# FPGA.net
KiCad netlist of a schematic drawn in Altium Designer
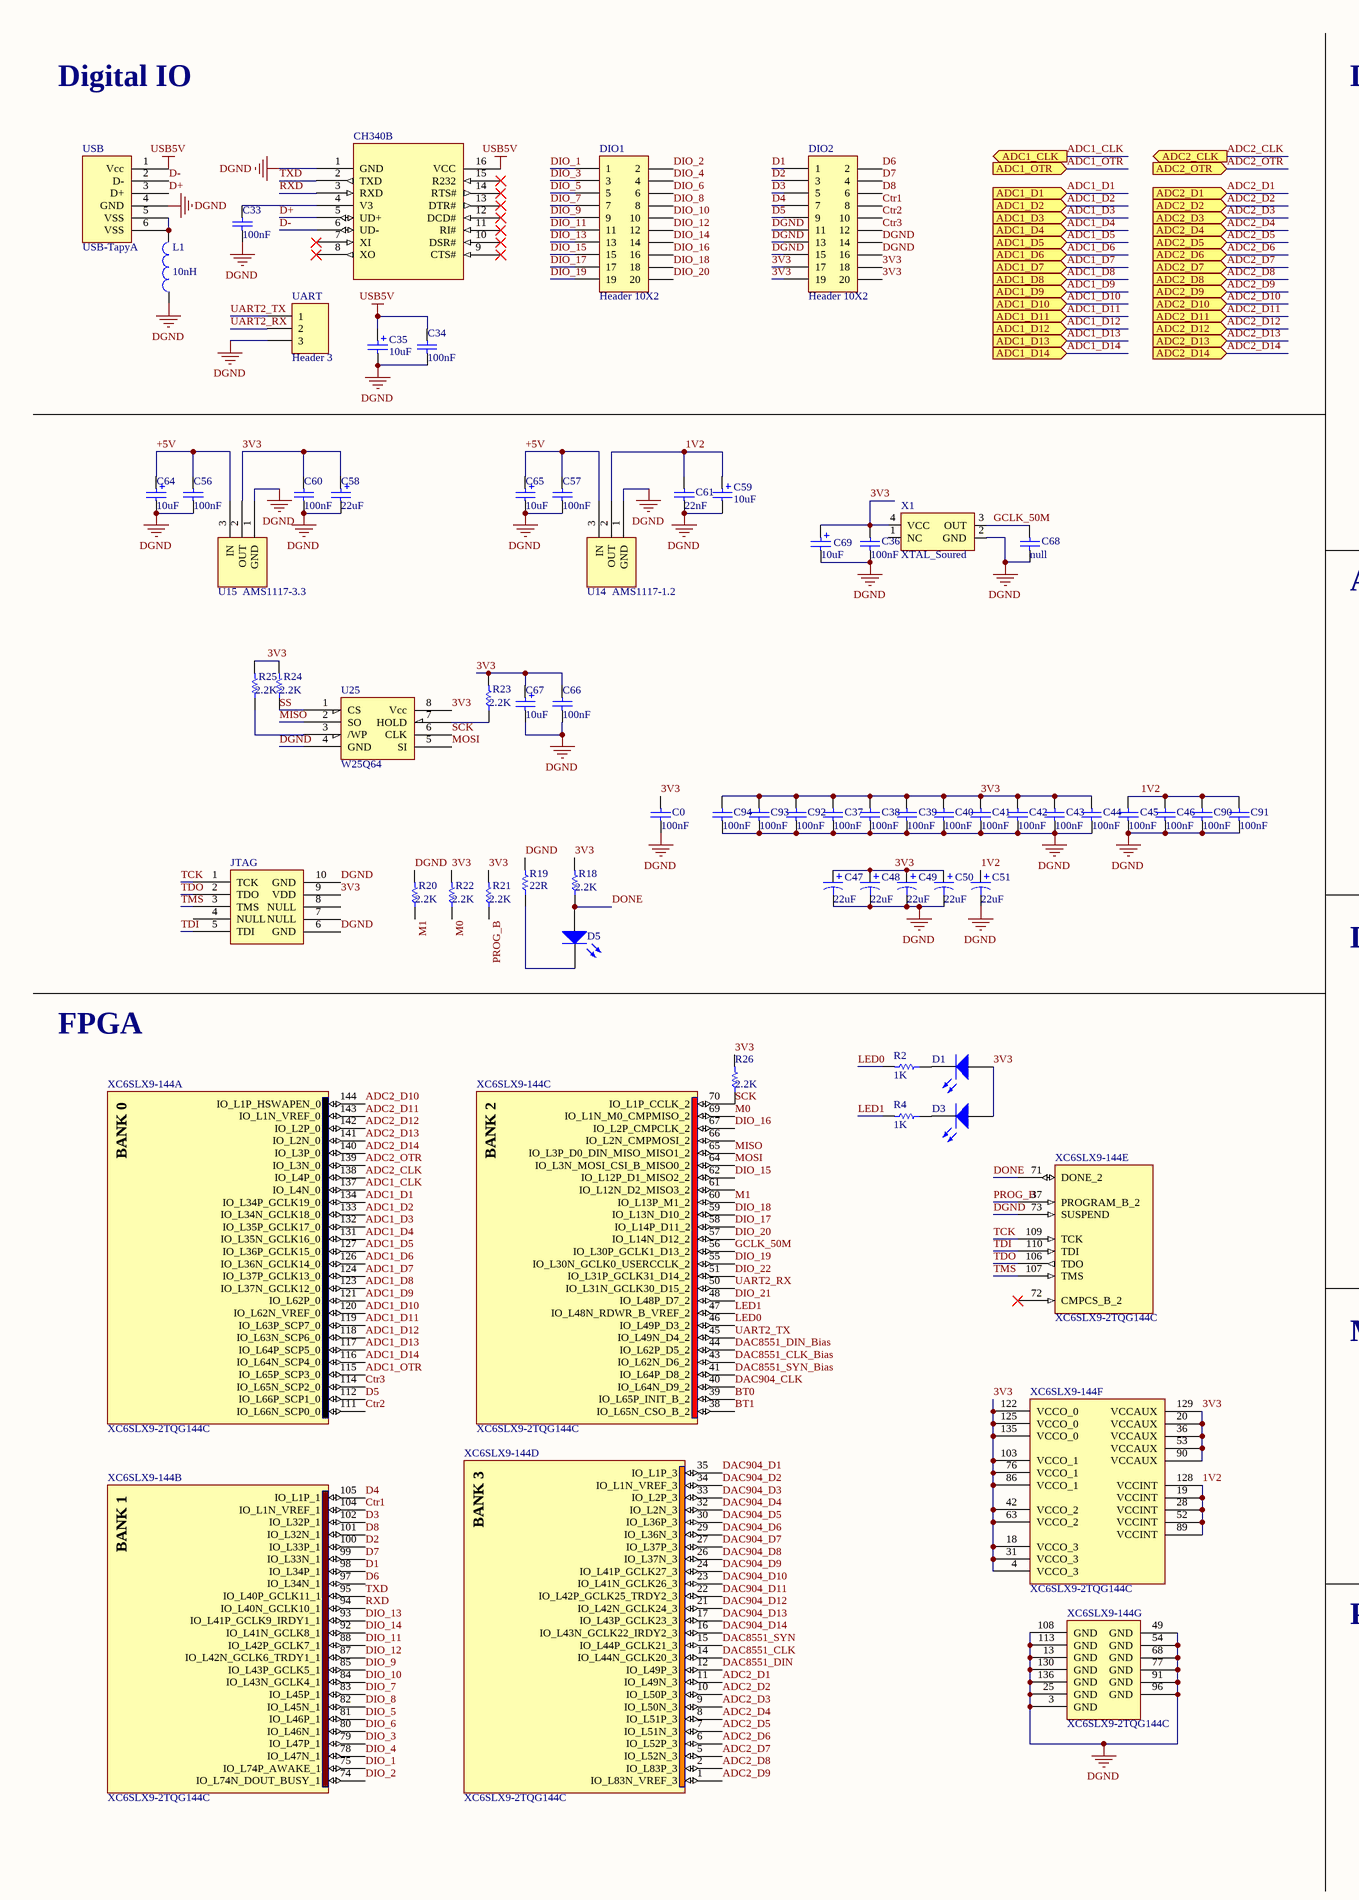
[diagram p0: FPGA.SchDoc, left]
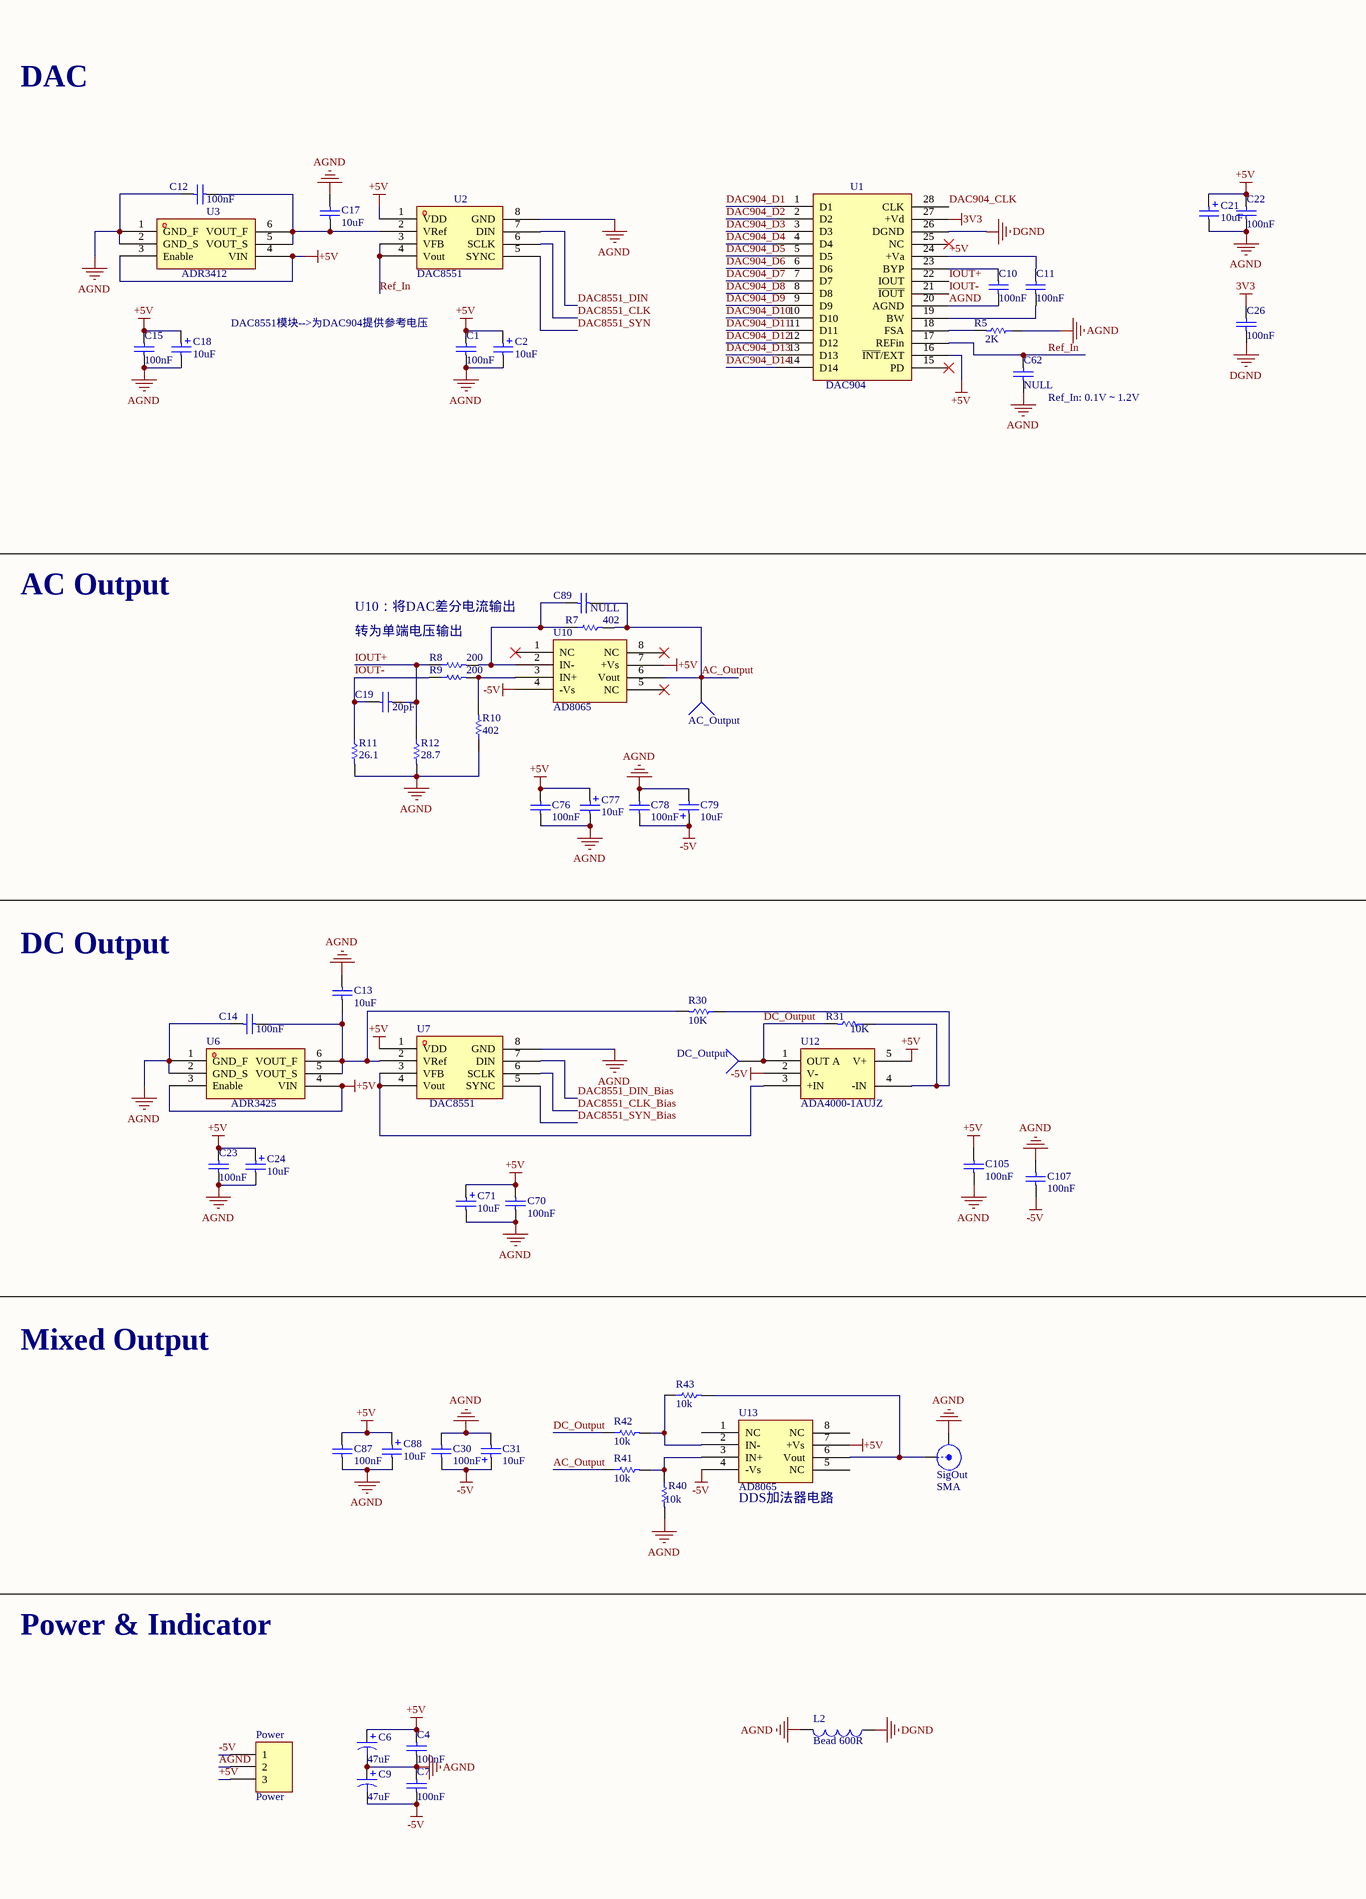
[diagram p1: FPGA.SchDoc, right]

(export (version "E")
  (design (tool "Eeschema 10.0.6"))
  (components
    (comp (ref "AC_Output")
      (value "OutDir")
      (footprint "PIN1")
      (description "Socket")
      (fields (field (name "PUBLISHER") "Altium Limited"))
      (libsource (lib "Miscellaneous Connectors") (part "Socket"))
    )
    (comp (ref "C0")
      (value "100nF")
      (footprint "BinFeng:0603")
      (description "Capacitor")
      (fields (field (name "PUBLISHER") "Altium Limited"))
      (libsource (lib "Miscellaneous Devices") (part "Cap"))
    )
    (comp (ref "C1")
      (value "100nF")
      (footprint "BinFeng:0603")
      (description "Capacitor (Semiconductor SIM Model)")
      (fields (field (name "PUBLISHER") "Altium Limited"))
      (libsource (lib "Miscellaneous Devices") (part "Cap Semi"))
    )
    (comp (ref "C2")
      (value "10uF")
      (footprint "3216")
      (description "Polarized Capacitor (Axial)")
      (fields (field (name "PUBLISHER") "Altium Limited"))
      (libsource (lib "Miscellaneous Devices") (part "Cap Pol2"))
    )
    (comp (ref "C4")
      (value "100nF")
      (footprint "SEEDER:0603")
      (description "Capacitor (Semiconductor SIM Model)")
      (fields (field (name "PUBLISHER") "Altium Limited"))
      (libsource (lib "Miscellaneous Devices") (part "Cap Semi"))
    )
    (comp (ref "C6")
      (value "47uF")
      (footprint "cap_pol_8*10.2")
      (description "Polarized Capacitor (Surface Mount)")
      (fields (field (name "PUBLISHER") "Altium Limited"))
      (libsource (lib "Miscellaneous Devices") (part "Cap Pol3"))
    )
    (comp (ref "C7")
      (value "100nF")
      (footprint "SEEDER:0603")
      (description "Capacitor (Semiconductor SIM Model)")
      (fields (field (name "PUBLISHER") "Altium Limited"))
      (libsource (lib "Miscellaneous Devices") (part "Cap Semi"))
    )
    (comp (ref "C9")
      (value "47uF")
      (footprint "cap_pol_8*10.2")
      (description "Polarized Capacitor (Surface Mount)")
      (fields (field (name "PUBLISHER") "Altium Limited"))
      (libsource (lib "Miscellaneous Devices") (part "Cap Pol3"))
    )
    (comp (ref "C10")
      (value "100nF")
      (footprint "BinFeng:0603")
      (description "Capacitor (Semiconductor SIM Model)")
      (fields (field (name "PUBLISHER") "Altium Limited"))
      (libsource (lib "Miscellaneous Devices") (part "Cap Semi"))
    )
    (comp (ref "C11")
      (value "100nF")
      (footprint "BinFeng:0603")
      (description "Capacitor (Semiconductor SIM Model)")
      (fields (field (name "PUBLISHER") "Altium Limited"))
      (libsource (lib "Miscellaneous Devices") (part "Cap Semi"))
    )
    (comp (ref "C12")
      (value "100nF")
      (footprint "BinFeng:0603")
      (description "Capacitor (Semiconductor SIM Model)")
      (fields (field (name "PUBLISHER") "Altium Limited"))
      (libsource (lib "Miscellaneous Devices") (part "Cap Semi"))
    )
    (comp (ref "C13")
      (value "10uF")
      (footprint "0805")
      (description "Capacitor (Semiconductor SIM Model)")
      (fields (field (name "PUBLISHER") "Altium Limited"))
      (libsource (lib "Miscellaneous Devices") (part "Cap Semi"))
    )
    (comp (ref "C14")
      (value "100nF")
      (footprint "BinFeng:0603")
      (description "Capacitor (Semiconductor SIM Model)")
      (fields (field (name "PUBLISHER") "Altium Limited"))
      (libsource (lib "Miscellaneous Devices") (part "Cap Semi"))
    )
    (comp (ref "C15")
      (value "100nF")
      (footprint "BinFeng:0603")
      (description "Capacitor (Semiconductor SIM Model)")
      (fields (field (name "PUBLISHER") "Altium Limited"))
      (libsource (lib "Miscellaneous Devices") (part "Cap Semi"))
    )
    (comp (ref "C17")
      (value "10uF")
      (footprint "0805")
      (description "Capacitor (Semiconductor SIM Model)")
      (fields (field (name "Comment") "100nF") (field (name "PUBLISHER") "Altium Limited"))
      (libsource (lib "Miscellaneous Devices") (part "Cap Semi"))
    )
    (comp (ref "C18")
      (value "10uF")
      (footprint "3216")
      (description "Polarized Capacitor (Axial)")
      (fields (field (name "PUBLISHER") "Altium Limited"))
      (libsource (lib "Miscellaneous Devices") (part "Cap Pol2"))
    )
    (comp (ref "C19")
      (value "20pF")
      (footprint "BinFeng:0603")
      (description "Capacitor (Semiconductor SIM Model)")
      (fields (field (name "PUBLISHER") "Altium Limited"))
      (libsource (lib "Miscellaneous Devices") (part "Cap Semi"))
    )
    (comp (ref "C21")
      (value "10uF")
      (footprint "3216")
      (description "Polarized Capacitor (Axial)")
      (fields (field (name "PUBLISHER") "Altium Limited"))
      (libsource (lib "Miscellaneous Devices") (part "Cap Pol2"))
    )
    (comp (ref "C22")
      (value "100nF")
      (footprint "BinFeng:0603")
      (description "Capacitor (Semiconductor SIM Model)")
      (fields (field (name "PUBLISHER") "Altium Limited"))
      (libsource (lib "Miscellaneous Devices") (part "Cap Semi"))
    )
    (comp (ref "C23")
      (value "100nF")
      (footprint "BinFeng:0603")
      (description "Capacitor (Semiconductor SIM Model)")
      (fields (field (name "PUBLISHER") "Altium Limited"))
      (libsource (lib "Miscellaneous Devices") (part "Cap Semi"))
    )
    (comp (ref "C24")
      (value "10uF")
      (footprint "3216")
      (description "Polarized Capacitor (Axial)")
      (fields (field (name "PUBLISHER") "Altium Limited"))
      (libsource (lib "Miscellaneous Devices") (part "Cap Pol2"))
    )
    (comp (ref "C26")
      (value "100nF")
      (footprint "BinFeng:0603")
      (description "Capacitor (Semiconductor SIM Model)")
      (fields (field (name "PUBLISHER") "Altium Limited"))
      (libsource (lib "Miscellaneous Devices") (part "Cap Semi"))
    )
    (comp (ref "C30")
      (value "100nF")
      (footprint "BinFeng:0603")
      (description "Capacitor (Semiconductor SIM Model)")
      (fields (field (name "PUBLISHER") "Altium Limited"))
      (libsource (lib "Miscellaneous Devices") (part "Cap Semi"))
    )
    (comp (ref "C31")
      (value "10uF")
      (footprint "3216")
      (description "Polarized Capacitor (Axial)")
      (fields (field (name "PUBLISHER") "Altium Limited"))
      (libsource (lib "Miscellaneous Devices") (part "Cap Pol2"))
    )
    (comp (ref "C33")
      (value "100nF")
      (footprint "SEEDER:0603")
      (description "Capacitor (Semiconductor SIM Model)")
      (fields (field (name "PUBLISHER") "Altium Limited"))
      (libsource (lib "Miscellaneous Devices") (part "Cap Semi"))
    )
    (comp (ref "C34")
      (value "100nF")
      (footprint "SEEDER:0603")
      (description "Capacitor (Semiconductor SIM Model)")
      (fields (field (name "PUBLISHER") "Altium Limited"))
      (libsource (lib "Miscellaneous Devices") (part "Cap Semi"))
    )
    (comp (ref "C35")
      (value "10uF")
      (footprint "3216")
      (description "Polarized Capacitor (Axial)")
      (fields (field (name "PUBLISHER") "Altium Limited"))
      (libsource (lib "Miscellaneous Devices") (part "Cap Pol2"))
    )
    (comp (ref "C36")
      (value "100nF")
      (footprint "BinFeng:0603")
      (description "Capacitor")
      (fields (field (name "PUBLISHER") "Altium Limited"))
      (libsource (lib "Miscellaneous Devices") (part "Cap"))
    )
    (comp (ref "C37")
      (value "100nF")
      (footprint "BinFeng:0603")
      (description "Capacitor")
      (fields (field (name "PUBLISHER") "Altium Limited"))
      (libsource (lib "Miscellaneous Devices") (part "Cap"))
    )
    (comp (ref "C38")
      (value "100nF")
      (footprint "BinFeng:0603")
      (description "Capacitor")
      (fields (field (name "PUBLISHER") "Altium Limited"))
      (libsource (lib "Miscellaneous Devices") (part "Cap"))
    )
    (comp (ref "C39")
      (value "100nF")
      (footprint "BinFeng:0603")
      (description "Capacitor")
      (fields (field (name "PUBLISHER") "Altium Limited"))
      (libsource (lib "Miscellaneous Devices") (part "Cap"))
    )
    (comp (ref "C40")
      (value "100nF")
      (footprint "BinFeng:0603")
      (description "Capacitor")
      (fields (field (name "PUBLISHER") "Altium Limited"))
      (libsource (lib "Miscellaneous Devices") (part "Cap"))
    )
    (comp (ref "C41")
      (value "100nF")
      (footprint "BinFeng:0603")
      (description "Capacitor")
      (fields (field (name "PUBLISHER") "Altium Limited"))
      (libsource (lib "Miscellaneous Devices") (part "Cap"))
    )
    (comp (ref "C42")
      (value "100nF")
      (footprint "BinFeng:0603")
      (description "Capacitor")
      (fields (field (name "PUBLISHER") "Altium Limited"))
      (libsource (lib "Miscellaneous Devices") (part "Cap"))
    )
    (comp (ref "C43")
      (value "100nF")
      (footprint "BinFeng:0603")
      (description "Capacitor")
      (fields (field (name "PUBLISHER") "Altium Limited"))
      (libsource (lib "Miscellaneous Devices") (part "Cap"))
    )
    (comp (ref "C44")
      (value "100nF")
      (footprint "BinFeng:0603")
      (description "Capacitor")
      (fields (field (name "PUBLISHER") "Altium Limited"))
      (libsource (lib "Miscellaneous Devices") (part "Cap"))
    )
    (comp (ref "C45")
      (value "100nF")
      (footprint "BinFeng:0603")
      (description "Capacitor")
      (fields (field (name "PUBLISHER") "Altium Limited"))
      (libsource (lib "Miscellaneous Devices") (part "Cap"))
    )
    (comp (ref "C46")
      (value "100nF")
      (footprint "BinFeng:0603")
      (description "Capacitor")
      (fields (field (name "PUBLISHER") "Altium Limited"))
      (libsource (lib "Miscellaneous Devices") (part "Cap"))
    )
    (comp (ref "C47")
      (value "22uF")
      (footprint "3216")
      (description "Polarized Capacitor (Surface Mount)")
      (fields (field (name "PUBLISHER") "Altium Limited"))
      (libsource (lib "Miscellaneous Devices") (part "Cap Pol3"))
    )
    (comp (ref "C48")
      (value "22uF")
      (footprint "3216")
      (description "Polarized Capacitor (Surface Mount)")
      (fields (field (name "PUBLISHER") "Altium Limited"))
      (libsource (lib "Miscellaneous Devices") (part "Cap Pol3"))
    )
    (comp (ref "C49")
      (value "22uF")
      (footprint "3216")
      (description "Polarized Capacitor (Surface Mount)")
      (fields (field (name "PUBLISHER") "Altium Limited"))
      (libsource (lib "Miscellaneous Devices") (part "Cap Pol3"))
    )
    (comp (ref "C50")
      (value "22uF")
      (footprint "3216")
      (description "Polarized Capacitor (Surface Mount)")
      (fields (field (name "PUBLISHER") "Altium Limited"))
      (libsource (lib "Miscellaneous Devices") (part "Cap Pol3"))
    )
    (comp (ref "C51")
      (value "22uF")
      (footprint "3216")
      (description "Polarized Capacitor (Surface Mount)")
      (fields (field (name "PUBLISHER") "Altium Limited"))
      (libsource (lib "Miscellaneous Devices") (part "Cap Pol3"))
    )
    (comp (ref "C56")
      (value "100nF")
      (footprint "BinFeng:0603")
      (description "Capacitor")
      (fields (field (name "PUBLISHER") "Altium Limited"))
      (libsource (lib "Miscellaneous Devices") (part "Cap"))
    )
    (comp (ref "C57")
      (value "100nF")
      (footprint "BinFeng:0603")
      (description "Capacitor")
      (fields (field (name "PUBLISHER") "Altium Limited"))
      (libsource (lib "Miscellaneous Devices") (part "Cap"))
    )
    (comp (ref "C58")
      (value "22uF")
      (footprint "3216")
      (description "Polarized Capacitor (Axial)")
      (fields (field (name "Comment") "10uF") (field (name "PUBLISHER") "Altium Limited"))
      (libsource (lib "Miscellaneous Devices") (part "Cap Pol2"))
    )
    (comp (ref "C59")
      (value "10uF")
      (footprint "3216")
      (description "Polarized Capacitor (Axial)")
      (fields (field (name "PUBLISHER") "Altium Limited"))
      (libsource (lib "Miscellaneous Devices") (part "Cap Pol2"))
    )
    (comp (ref "C60")
      (value "100nF")
      (footprint "BinFeng:0603")
      (description "Capacitor")
      (fields (field (name "PUBLISHER") "Altium Limited"))
      (libsource (lib "Miscellaneous Devices") (part "Cap"))
    )
    (comp (ref "C61")
      (value "22nF")
      (footprint "BinFeng:0603")
      (description "Capacitor")
      (fields (field (name "PUBLISHER") "Altium Limited"))
      (libsource (lib "Miscellaneous Devices") (part "Cap"))
    )
    (comp (ref "C62")
      (value "NULL")
      (footprint "BinFeng:0603")
      (description "Capacitor (Semiconductor SIM Model)")
      (fields (field (name "Comment") "100nF") (field (name "PUBLISHER") "Altium Limited"))
      (libsource (lib "Miscellaneous Devices") (part "Cap Semi"))
    )
    (comp (ref "C64")
      (value "10uF")
      (footprint "3216")
      (description "Polarized Capacitor (Axial)")
      (fields (field (name "PUBLISHER") "Altium Limited"))
      (libsource (lib "Miscellaneous Devices") (part "Cap Pol2"))
    )
    (comp (ref "C65")
      (value "10uF")
      (footprint "3216")
      (description "Polarized Capacitor (Axial)")
      (fields (field (name "PUBLISHER") "Altium Limited"))
      (libsource (lib "Miscellaneous Devices") (part "Cap Pol2"))
    )
    (comp (ref "C66")
      (value "100nF")
      (footprint "BinFeng:0603")
      (description "Capacitor")
      (fields (field (name "PUBLISHER") "Altium Limited"))
      (libsource (lib "Miscellaneous Devices") (part "Cap"))
    )
    (comp (ref "C67")
      (value "10uF")
      (footprint "3216")
      (description "Polarized Capacitor (Axial)")
      (fields (field (name "PUBLISHER") "Altium Limited"))
      (libsource (lib "Miscellaneous Devices") (part "Cap Pol2"))
    )
    (comp (ref "C68")
      (value "null")
      (footprint "BinFeng:0603")
      (description "Capacitor")
      (fields (field (name "Comment") "100nF") (field (name "PUBLISHER") "Altium Limited"))
      (libsource (lib "Miscellaneous Devices") (part "Cap"))
    )
    (comp (ref "C69")
      (value "10uF")
      (footprint "3216")
      (description "Polarized Capacitor (Axial)")
      (fields (field (name "PUBLISHER") "Altium Limited"))
      (libsource (lib "Miscellaneous Devices") (part "Cap Pol2"))
    )
    (comp (ref "C70")
      (value "100nF")
      (footprint "BinFeng:0603")
      (description "Capacitor (Semiconductor SIM Model)")
      (fields (field (name "PUBLISHER") "Altium Limited"))
      (libsource (lib "Miscellaneous Devices") (part "Cap Semi"))
    )
    (comp (ref "C71")
      (value "10uF")
      (footprint "3216")
      (description "Polarized Capacitor (Axial)")
      (fields (field (name "PUBLISHER") "Altium Limited"))
      (libsource (lib "Miscellaneous Devices") (part "Cap Pol2"))
    )
    (comp (ref "C76")
      (value "100nF")
      (footprint "BinFeng:0603")
      (description "Capacitor (Semiconductor SIM Model)")
      (fields (field (name "PUBLISHER") "Altium Limited"))
      (libsource (lib "Miscellaneous Devices") (part "Cap Semi"))
    )
    (comp (ref "C77")
      (value "10uF")
      (footprint "3216")
      (description "Polarized Capacitor (Axial)")
      (fields (field (name "PUBLISHER") "Altium Limited"))
      (libsource (lib "Miscellaneous Devices") (part "Cap Pol2"))
    )
    (comp (ref "C78")
      (value "100nF")
      (footprint "BinFeng:0603")
      (description "Capacitor (Semiconductor SIM Model)")
      (fields (field (name "PUBLISHER") "Altium Limited"))
      (libsource (lib "Miscellaneous Devices") (part "Cap Semi"))
    )
    (comp (ref "C79")
      (value "10uF")
      (footprint "3216")
      (description "Polarized Capacitor (Axial)")
      (fields (field (name "PUBLISHER") "Altium Limited"))
      (libsource (lib "Miscellaneous Devices") (part "Cap Pol2"))
    )
    (comp (ref "C87")
      (value "100nF")
      (footprint "BinFeng:0603")
      (description "Capacitor (Semiconductor SIM Model)")
      (fields (field (name "PUBLISHER") "Altium Limited"))
      (libsource (lib "Miscellaneous Devices") (part "Cap Semi"))
    )
    (comp (ref "C88")
      (value "10uF")
      (footprint "3216")
      (description "Polarized Capacitor (Axial)")
      (fields (field (name "PUBLISHER") "Altium Limited"))
      (libsource (lib "Miscellaneous Devices") (part "Cap Pol2"))
    )
    (comp (ref "C89")
      (value "NULL")
      (footprint "BinFeng:0603")
      (description "Capacitor (Semiconductor SIM Model)")
      (fields (field (name "PUBLISHER") "Altium Limited"))
      (libsource (lib "Miscellaneous Devices") (part "Cap Semi"))
    )
    (comp (ref "C90")
      (value "100nF")
      (footprint "BinFeng:0603")
      (description "Capacitor")
      (fields (field (name "PUBLISHER") "Altium Limited"))
      (libsource (lib "Miscellaneous Devices") (part "Cap"))
    )
    (comp (ref "C91")
      (value "100nF")
      (footprint "BinFeng:0603")
      (description "Capacitor")
      (fields (field (name "PUBLISHER") "Altium Limited"))
      (libsource (lib "Miscellaneous Devices") (part "Cap"))
    )
    (comp (ref "C92")
      (value "100nF")
      (footprint "BinFeng:0603")
      (description "Capacitor")
      (fields (field (name "PUBLISHER") "Altium Limited"))
      (libsource (lib "Miscellaneous Devices") (part "Cap"))
    )
    (comp (ref "C93")
      (value "100nF")
      (footprint "BinFeng:0603")
      (description "Capacitor")
      (fields (field (name "PUBLISHER") "Altium Limited"))
      (libsource (lib "Miscellaneous Devices") (part "Cap"))
    )
    (comp (ref "C94")
      (value "100nF")
      (footprint "BinFeng:0603")
      (description "Capacitor")
      (fields (field (name "PUBLISHER") "Altium Limited"))
      (libsource (lib "Miscellaneous Devices") (part "Cap"))
    )
    (comp (ref "C105")
      (value "100nF")
      (footprint "BinFeng:0603")
      (description "Capacitor (Semiconductor SIM Model)")
      (fields (field (name "PUBLISHER") "Altium Limited"))
      (libsource (lib "Miscellaneous Devices") (part "Cap Semi"))
    )
    (comp (ref "C107")
      (value "100nF")
      (footprint "BinFeng:0603")
      (description "Capacitor (Semiconductor SIM Model)")
      (fields (field (name "PUBLISHER") "Altium Limited"))
      (libsource (lib "Miscellaneous Devices") (part "Cap Semi"))
    )
    (comp (ref "CH340B")
      (value "Comment")
      (footprint "PCBComponent_1")
      (description "USB to TTL Serial / UART")
      (libsource (lib "*") (part "CH340G"))
    )
    (comp (ref "D1")
      (value "LED3")
      (footprint "1206_LED")
      (description "Typical BLUE SiC LED")
      (fields (field (name "PUBLISHER") "Altium Limited"))
      (libsource (lib "Miscellaneous Devices") (part "LED3"))
    )
    (comp (ref "D3")
      (value "LED3")
      (footprint "1206_LED")
      (description "Typical BLUE SiC LED")
      (fields (field (name "PUBLISHER") "Altium Limited"))
      (libsource (lib "Miscellaneous Devices") (part "LED3"))
    )
    (comp (ref "D5")
      (value "LED3")
      (footprint "0805_pol1")
      (description "Typical BLUE SiC LED")
      (fields (field (name "PUBLISHER") "Altium Limited"))
      (libsource (lib "Miscellaneous Devices") (part "LED3"))
    )
    (comp (ref "DC_Output")
      (value "OutDir")
      (footprint "PIN1")
      (description "Socket")
      (fields (field (name "PUBLISHER") "Altium Limited"))
      (libsource (lib "Miscellaneous Connectors") (part "Socket"))
    )
    (comp (ref "DIO1")
      (value "Header 10X2")
      (footprint "HDR2X10")
      (description "Header, 10-Pin, Dual row")
      (fields (field (name "PUBLISHER") "Altium Limited"))
      (libsource (lib "Miscellaneous Connectors") (part "Header 10X2"))
    )
    (comp (ref "DIO2")
      (value "Header 10X2")
      (footprint "HDR2X10")
      (description "Header, 10-Pin, Dual row")
      (fields (field (name "PUBLISHER") "Altium Limited"))
      (libsource (lib "Miscellaneous Connectors") (part "Header 10X2"))
    )
    (comp (ref "JTAG")
      (value "JTAG 2*5p 2.00mm 180 degree")
      (footprint "JTAG_2.54_2x5")
      (libsource (lib "BinFeng_IC") (part "FPGA_JTAG"))
    )
    (comp (ref "L1")
      (value "10nH")
      (footprint "0805")
      (description "Inductor")
      (fields (field (name "PUBLISHER") "Altium Limited"))
      (libsource (lib "Miscellaneous Devices") (part "Inductor"))
    )
    (comp (ref "L2")
      (value "Bead 600R")
      (footprint "0805")
      (description "Inductor")
      (fields (field (name "Comment") "10nH") (field (name "PUBLISHER") "Altium Limited"))
      (libsource (lib "Miscellaneous Devices") (part "Inductor"))
    )
    (comp (ref "Power")
      (value "Power")
      (footprint "PWR_3T")
      (description "Header, 3-Pin")
      (fields (field (name "PUBLISHER") "Altium Limited"))
      (libsource (lib "Miscellaneous Connectors") (part "Header 3"))
    )
    (comp (ref "R2")
      (value "1K")
      (footprint "BinFeng:0603")
      (description "Resistor")
      (fields (field (name "Comment") "2.2K") (field (name "PUBLISHER") "Altium Limited"))
      (libsource (lib "Miscellaneous Devices") (part "Res1"))
    )
    (comp (ref "R4")
      (value "1K")
      (footprint "BinFeng:0603")
      (description "Resistor")
      (fields (field (name "Comment") "2.2K") (field (name "PUBLISHER") "Altium Limited"))
      (libsource (lib "Miscellaneous Devices") (part "Res1"))
    )
    (comp (ref "R5")
      (value "2K")
      (footprint "BinFeng:0603")
      (description "Resistor")
      (fields (field (name "Comment") "4.7K") (field (name "PUBLISHER") "Altium Limited"))
      (libsource (lib "Miscellaneous Devices") (part "Res1"))
    )
    (comp (ref "R7")
      (value "402")
      (footprint "BinFeng:0603")
      (description "Resistor")
      (fields (field (name "PUBLISHER") "Altium Limited"))
      (libsource (lib "Miscellaneous Devices") (part "Res1"))
    )
    (comp (ref "R8")
      (value "200")
      (footprint "BinFeng:0603")
      (description "Resistor")
      (fields (field (name "PUBLISHER") "Altium Limited"))
      (libsource (lib "Miscellaneous Devices") (part "Res1"))
    )
    (comp (ref "R9")
      (value "200")
      (footprint "BinFeng:0603")
      (description "Resistor")
      (fields (field (name "PUBLISHER") "Altium Limited"))
      (libsource (lib "Miscellaneous Devices") (part "Res1"))
    )
    (comp (ref "R10")
      (value "402")
      (footprint "BinFeng:0603")
      (description "Resistor")
      (fields (field (name "PUBLISHER") "Altium Limited"))
      (libsource (lib "Miscellaneous Devices") (part "Res1"))
    )
    (comp (ref "R11")
      (value "26.1")
      (footprint "BinFeng:0603")
      (description "Resistor")
      (fields (field (name "PUBLISHER") "Altium Limited"))
      (libsource (lib "Miscellaneous Devices") (part "Res1"))
    )
    (comp (ref "R12")
      (value "28.7")
      (footprint "BinFeng:0603")
      (description "Resistor")
      (fields (field (name "PUBLISHER") "Altium Limited"))
      (libsource (lib "Miscellaneous Devices") (part "Res1"))
    )
    (comp (ref "R18")
      (value "2.2K")
      (footprint "BinFeng:0603")
      (description "Resistor")
      (fields (field (name "PUBLISHER") "Altium Limited"))
      (libsource (lib "Miscellaneous Devices") (part "Res1"))
    )
    (comp (ref "R19")
      (value "22R")
      (footprint "BinFeng:0603")
      (description "Resistor")
      (fields (field (name "PUBLISHER") "Altium Limited"))
      (libsource (lib "Miscellaneous Devices") (part "Res1"))
    )
    (comp (ref "R20")
      (value "2.2K")
      (footprint "BinFeng:0603")
      (description "Resistor")
      (fields (field (name "PUBLISHER") "Altium Limited"))
      (libsource (lib "Miscellaneous Devices") (part "Res1"))
    )
    (comp (ref "R21")
      (value "2.2K")
      (footprint "BinFeng:0603")
      (description "Resistor")
      (fields (field (name "PUBLISHER") "Altium Limited"))
      (libsource (lib "Miscellaneous Devices") (part "Res1"))
    )
    (comp (ref "R22")
      (value "2.2K")
      (footprint "BinFeng:0603")
      (description "Resistor")
      (fields (field (name "PUBLISHER") "Altium Limited"))
      (libsource (lib "Miscellaneous Devices") (part "Res1"))
    )
    (comp (ref "R23")
      (value "2.2K")
      (footprint "BinFeng:0603")
      (description "Resistor")
      (fields (field (name "PUBLISHER") "Altium Limited"))
      (libsource (lib "Miscellaneous Devices") (part "Res1"))
    )
    (comp (ref "R24")
      (value "2.2K")
      (footprint "BinFeng:0603")
      (description "Resistor")
      (fields (field (name "PUBLISHER") "Altium Limited"))
      (libsource (lib "Miscellaneous Devices") (part "Res1"))
    )
    (comp (ref "R25")
      (value "2.2K")
      (footprint "BinFeng:0603")
      (description "Resistor")
      (fields (field (name "PUBLISHER") "Altium Limited"))
      (libsource (lib "Miscellaneous Devices") (part "Res1"))
    )
    (comp (ref "R26")
      (value "2.2K")
      (footprint "BinFeng:0603")
      (description "Resistor")
      (fields (field (name "PUBLISHER") "Altium Limited"))
      (libsource (lib "Miscellaneous Devices") (part "Res1"))
    )
    (comp (ref "R30")
      (value "10K")
      (footprint "BinFeng:0603")
      (description "Resistor")
      (fields (field (name "PUBLISHER") "Altium Limited"))
      (libsource (lib "Miscellaneous Devices") (part "Res1"))
    )
    (comp (ref "R31")
      (value "10K")
      (footprint "BinFeng:0603")
      (description "Resistor")
      (fields (field (name "PUBLISHER") "Altium Limited"))
      (libsource (lib "Miscellaneous Devices") (part "Res1"))
    )
    (comp (ref "R40")
      (value "10k")
      (footprint "BinFeng:0603")
      (description "Resistor")
      (fields (field (name "PUBLISHER") "Altium Limited"))
      (libsource (lib "Miscellaneous Devices") (part "Res1"))
    )
    (comp (ref "R41")
      (value "10k")
      (footprint "BinFeng:0603")
      (description "Resistor")
      (fields (field (name "PUBLISHER") "Altium Limited"))
      (libsource (lib "Miscellaneous Devices") (part "Res1"))
    )
    (comp (ref "R42")
      (value "10k")
      (footprint "BinFeng:0603")
      (description "Resistor")
      (fields (field (name "PUBLISHER") "Altium Limited"))
      (libsource (lib "Miscellaneous Devices") (part "Res1"))
    )
    (comp (ref "R43")
      (value "10k")
      (footprint "BinFeng:0603")
      (description "Resistor")
      (fields (field (name "PUBLISHER") "Altium Limited"))
      (libsource (lib "Miscellaneous Devices") (part "Res1"))
    )
    (comp (ref "SigOut")
      (value "SMA")
      (footprint "SMA_SMT")
      (description "BNC Elbow Connector")
      (fields (field (name "PUBLISHER") "Altium Limited"))
      (libsource (lib "Miscellaneous Connectors") (part "BNC"))
    )
    (comp (ref "U1") (value "DAC904") (footprint "TSSOP-28") (libsource (lib "MySch") (part "DAC90X")))
    (comp (ref "U2") (value "DAC8551") (footprint "VSSOP-8") (libsource (lib "AD5680") (part "AD5680")))
    (comp (ref "U3") (value "ADR3412") (footprint "SOT23-6") (libsource (lib "AD5680") (part "ADR34xx")))
    (comp (ref "U6") (value "ADR3425") (footprint "SOT23-6") (libsource (lib "AD5680") (part "ADR34xx")))
    (comp (ref "U7") (value "DAC8551") (footprint "VSSOP-8") (libsource (lib "AD5680") (part "AD5680")))
    (comp (ref "U10")
      (value "AD8065")
      (footprint "SO-8N")
      (description "High Speed JFET Input Amplifier")
      (libsource (lib "BinFeng_IC") (part "AD8065"))
    )
    (comp (ref "U12")
      (value "ADA4000-1AUJZ")
      (footprint "SOT-23-5")
      (description "Precision CMOS, Single Supply, Rail to Rail, Windband Operational Amplifiers")
      (libsource (lib "BinFeng_IC") (part "AD8601"))
    )
    (comp (ref "U13")
      (value "AD8065")
      (footprint "SO-8N")
      (description "High Speed JFET Input Amplifier")
      (libsource (lib "BinFeng_IC") (part "AD8065"))
    )
    (comp (ref "U14")
      (value "AMS1117-1.2")
      (footprint "SOT-223")
      (libsource (lib "BinFeng_IC") (part "AMS1117"))
    )
    (comp (ref "U15")
      (value "AMS1117-3.3")
      (footprint "SOT-223")
      (libsource (lib "BinFeng_IC") (part "AMS1117"))
    )
    (comp (ref "U25") (value "W25Q64") (footprint "SO-8M") (libsource (lib "BinFeng_IC") (part "W25X16")))
    (comp (ref "UART")
      (value "Header 3")
      (footprint "HDR1X3")
      (description "Header, 3-Pin")
      (fields (field (name "PUBLISHER") "Altium Limited"))
      (libsource (lib "Miscellaneous Connectors") (part "Header 3"))
    )
    (comp (ref "USB") (value "USB-TapyA") (libsource (lib "ECS_V2") (part "USB-TapyA")))
    (comp (ref "X1")
      (value "XTAL_Soured")
      (footprint "XTAL3225")
      (libsource (lib "BinFeng_IC") (part "XTAL_Soured"))
    )
    (comp (ref "XC6SLX9-144")
      (value "XC6SLX9-2TQG144C")
      (footprint "TQG144_N")
      (fields (field (name "PUBLISHER") "Altium Limited"))
      (libsource (lib "Xilinx Spartan-6") (part "XC6SLX9-2TQG144C"))
    )
  )
  (nets
    (net (code "1") (name "+5V") (class "Default")
      (node (ref "C1") (pin "2") (pinfunction "2_2") (pintype "passive"))
      (node (ref "C105") (pin "2") (pinfunction "2_2") (pintype "passive"))
      (node (ref "C11") (pin "1") (pinfunction "1_1") (pintype "passive"))
      (node (ref "C15") (pin "1") (pinfunction "1_1") (pintype "passive"))
      (node (ref "C18") (pin "1") (pinfunction "1_1") (pintype "passive"))
      (node (ref "C2") (pin "1") (pinfunction "1_1") (pintype "passive"))
      (node (ref "C21") (pin "1") (pinfunction "1_1") (pintype "passive"))
      (node (ref "C22") (pin "1") (pinfunction "1_1") (pintype "passive"))
      (node (ref "C23") (pin "1") (pinfunction "1_1") (pintype "passive"))
      (node (ref "C24") (pin "1") (pinfunction "1_1") (pintype "passive"))
      (node (ref "C4") (pin "1") (pinfunction "1_1") (pintype "passive"))
      (node (ref "C56") (pin "2") (pinfunction "2_2") (pintype "passive"))
      (node (ref "C57") (pin "2") (pinfunction "2_2") (pintype "passive"))
      (node (ref "C6") (pin "1") (pinfunction "1_1") (pintype "passive"))
      (node (ref "C64") (pin "1") (pinfunction "1_1") (pintype "passive"))
      (node (ref "C65") (pin "1") (pinfunction "1_1") (pintype "passive"))
      (node (ref "C70") (pin "1") (pinfunction "1_1") (pintype "passive"))
      (node (ref "C71") (pin "1") (pinfunction "1_1") (pintype "passive"))
      (node (ref "C76") (pin "2") (pinfunction "2_2") (pintype "passive"))
      (node (ref "C77") (pin "1") (pinfunction "1_1") (pintype "passive"))
      (node (ref "C87") (pin "2") (pinfunction "2_2") (pintype "passive"))
      (node (ref "C88") (pin "1") (pinfunction "1_1") (pintype "passive"))
      (node (ref "Power") (pin "3") (pinfunction "3_3") (pintype "passive"))
      (node (ref "U1") (pin "16") (pinfunction "~{INT}/EXT_16") (pintype "passive"))
      (node (ref "U1") (pin "24") (pinfunction "+Va_24") (pintype "passive"))
      (node (ref "U10") (pin "7") (pinfunction "+Vs_7") (pintype "passive"))
      (node (ref "U12") (pin "5") (pinfunction "V+_5") (pintype "passive"))
      (node (ref "U13") (pin "7") (pinfunction "+Vs_7") (pintype "passive"))
      (node (ref "U14") (pin "3") (pinfunction "IN_3") (pintype "passive"))
      (node (ref "U15") (pin "3") (pinfunction "IN_3") (pintype "passive"))
      (node (ref "U2") (pin "1") (pinfunction "VDD_1") (pintype "passive"))
      (node (ref "U3") (pin "3") (pinfunction "Enable_3") (pintype "passive"))
      (node (ref "U3") (pin "4") (pinfunction "VIN_4") (pintype "passive"))
      (node (ref "U6") (pin "3") (pinfunction "Enable_3") (pintype "passive"))
      (node (ref "U6") (pin "4") (pinfunction "VIN_4") (pintype "passive"))
      (node (ref "U7") (pin "1") (pinfunction "VDD_1") (pintype "passive"))
    )
    (net (code "2") (name "-5V") (class "Default")
      (node (ref "C107") (pin "1") (pinfunction "1_1") (pintype "passive"))
      (node (ref "C30") (pin "1") (pinfunction "1_1") (pintype "passive"))
      (node (ref "C31") (pin "1") (pinfunction "1_1") (pintype "passive"))
      (node (ref "C7") (pin "2") (pinfunction "2_2") (pintype "passive"))
      (node (ref "C78") (pin "1") (pinfunction "1_1") (pintype "passive"))
      (node (ref "C79") (pin "1") (pinfunction "1_1") (pintype "passive"))
      (node (ref "C9") (pin "2") (pinfunction "2_2") (pintype "passive"))
      (node (ref "Power") (pin "1") (pinfunction "1_1") (pintype "passive"))
      (node (ref "U10") (pin "4") (pinfunction "-Vs_4") (pintype "passive"))
      (node (ref "U12") (pin "2") (pinfunction "V-_2") (pintype "passive"))
      (node (ref "U13") (pin "4") (pinfunction "-Vs_4") (pintype "passive"))
    )
    (net (code "3") (name "/1V2") (class "Default")
      (node (ref "C45") (pin "2") (pinfunction "2_2") (pintype "passive"))
      (node (ref "C46") (pin "2") (pinfunction "2_2") (pintype "passive"))
      (node (ref "C51") (pin "1") (pinfunction "1_1") (pintype "passive"))
      (node (ref "C59") (pin "1") (pinfunction "1_1") (pintype "passive"))
      (node (ref "C61") (pin "2") (pinfunction "2_2") (pintype "passive"))
      (node (ref "C90") (pin "2") (pinfunction "2_2") (pintype "passive"))
      (node (ref "C91") (pin "2") (pinfunction "2_2") (pintype "passive"))
      (node (ref "U14") (pin "2") (pinfunction "OUT_2") (pintype "passive"))
      (node (ref "XC6SLX9-144") (pin "128") (pinfunction "VCCINT_128") (pintype "power_in"))
      (node (ref "XC6SLX9-144") (pin "19") (pinfunction "VCCINT_19") (pintype "power_in"))
      (node (ref "XC6SLX9-144") (pin "28") (pinfunction "VCCINT_28") (pintype "power_in"))
      (node (ref "XC6SLX9-144") (pin "52") (pinfunction "VCCINT_52") (pintype "power_in"))
      (node (ref "XC6SLX9-144") (pin "89") (pinfunction "VCCINT_89") (pintype "power_in"))
    )
    (net (code "4") (name "/AC_Output") (class "Default")
      (node (ref "AC_Output") (pin "1") (pinfunction "1_1") (pintype "passive"))
      (node (ref "C89") (pin "2") (pinfunction "2_2") (pintype "passive"))
      (node (ref "R41") (pin "1") (pinfunction "1_1") (pintype "passive"))
      (node (ref "R7") (pin "2") (pinfunction "2_2") (pintype "passive"))
      (node (ref "U10") (pin "6") (pinfunction "Vout_6") (pintype "passive"))
    )
    (net (code "5") (name "/ADC1_CLK") (class "Default")
      (node (ref "XC6SLX9-144") (pin "137") (pinfunction "IO_L4N_0_137") (pintype "bidirectional"))
    )
    (net (code "6") (name "/ADC1_D1") (class "Default")
      (node (ref "XC6SLX9-144") (pin "134") (pinfunction "IO_L34P_GCLK19_0_134") (pintype "bidirectional"))
    )
    (net (code "7") (name "/ADC1_D2") (class "Default")
      (node (ref "XC6SLX9-144") (pin "133") (pinfunction "IO_L34N_GCLK18_0_133") (pintype "bidirectional"))
    )
    (net (code "8") (name "/ADC1_D3") (class "Default")
      (node (ref "XC6SLX9-144") (pin "132") (pinfunction "IO_L35P_GCLK17_0_132") (pintype "bidirectional"))
    )
    (net (code "9") (name "/ADC1_D4") (class "Default")
      (node (ref "XC6SLX9-144") (pin "131") (pinfunction "IO_L35N_GCLK16_0_131") (pintype "bidirectional"))
    )
    (net (code "10") (name "/ADC1_D5") (class "Default")
      (node (ref "XC6SLX9-144") (pin "127") (pinfunction "IO_L36P_GCLK15_0_127") (pintype "bidirectional"))
    )
    (net (code "11") (name "/ADC1_D6") (class "Default")
      (node (ref "XC6SLX9-144") (pin "126") (pinfunction "IO_L36N_GCLK14_0_126") (pintype "bidirectional"))
    )
    (net (code "12") (name "/ADC1_D7") (class "Default")
      (node (ref "XC6SLX9-144") (pin "124") (pinfunction "IO_L37P_GCLK13_0_124") (pintype "bidirectional"))
    )
    (net (code "13") (name "/ADC1_D8") (class "Default")
      (node (ref "XC6SLX9-144") (pin "123") (pinfunction "IO_L37N_GCLK12_0_123") (pintype "bidirectional"))
    )
    (net (code "14") (name "/ADC1_D9") (class "Default")
      (node (ref "XC6SLX9-144") (pin "121") (pinfunction "IO_L62P_0_121") (pintype "bidirectional"))
    )
    (net (code "15") (name "/ADC1_D10") (class "Default")
      (node (ref "XC6SLX9-144") (pin "120") (pinfunction "IO_L62N_VREF_0_120") (pintype "bidirectional"))
    )
    (net (code "16") (name "/ADC1_D11") (class "Default")
      (node (ref "XC6SLX9-144") (pin "119") (pinfunction "IO_L63P_SCP7_0_119") (pintype "bidirectional"))
    )
    (net (code "17") (name "/ADC1_D12") (class "Default")
      (node (ref "XC6SLX9-144") (pin "118") (pinfunction "IO_L63N_SCP6_0_118") (pintype "bidirectional"))
    )
    (net (code "18") (name "/ADC1_D13") (class "Default")
      (node (ref "XC6SLX9-144") (pin "117") (pinfunction "IO_L64P_SCP5_0_117") (pintype "bidirectional"))
    )
    (net (code "19") (name "/ADC1_D14") (class "Default")
      (node (ref "XC6SLX9-144") (pin "116") (pinfunction "IO_L64N_SCP4_0_116") (pintype "bidirectional"))
    )
    (net (code "20") (name "/ADC1_OTR") (class "Default")
      (node (ref "XC6SLX9-144") (pin "115") (pinfunction "IO_L65P_SCP3_0_115") (pintype "bidirectional"))
    )
    (net (code "21") (name "/ADC2_CLK") (class "Default")
      (node (ref "XC6SLX9-144") (pin "138") (pinfunction "IO_L4P_0_138") (pintype "bidirectional"))
    )
    (net (code "22") (name "/ADC2_D1") (class "Default")
      (node (ref "XC6SLX9-144") (pin "11") (pinfunction "IO_L49N_3_11") (pintype "bidirectional"))
    )
    (net (code "23") (name "/ADC2_D2") (class "Default")
      (node (ref "XC6SLX9-144") (pin "10") (pinfunction "IO_L50P_3_10") (pintype "bidirectional"))
    )
    (net (code "24") (name "/ADC2_D3") (class "Default")
      (node (ref "XC6SLX9-144") (pin "9") (pinfunction "IO_L50N_3_9") (pintype "bidirectional"))
    )
    (net (code "25") (name "/ADC2_D4") (class "Default")
      (node (ref "XC6SLX9-144") (pin "8") (pinfunction "IO_L51P_3_8") (pintype "bidirectional"))
    )
    (net (code "26") (name "/ADC2_D5") (class "Default")
      (node (ref "XC6SLX9-144") (pin "7") (pinfunction "IO_L51N_3_7") (pintype "bidirectional"))
    )
    (net (code "27") (name "/ADC2_D6") (class "Default")
      (node (ref "XC6SLX9-144") (pin "6") (pinfunction "IO_L52P_3_6") (pintype "bidirectional"))
    )
    (net (code "28") (name "/ADC2_D7") (class "Default")
      (node (ref "XC6SLX9-144") (pin "5") (pinfunction "IO_L52N_3_5") (pintype "bidirectional"))
    )
    (net (code "29") (name "/ADC2_D8") (class "Default")
      (node (ref "XC6SLX9-144") (pin "2") (pinfunction "IO_L83P_3_2") (pintype "bidirectional"))
    )
    (net (code "30") (name "/ADC2_D9") (class "Default")
      (node (ref "XC6SLX9-144") (pin "1") (pinfunction "IO_L83N_VREF_3_1") (pintype "bidirectional"))
    )
    (net (code "31") (name "/ADC2_D10") (class "Default")
      (node (ref "XC6SLX9-144") (pin "144") (pinfunction "IO_L1P_HSWAPEN_0_144") (pintype "bidirectional"))
    )
    (net (code "32") (name "/ADC2_D11") (class "Default")
      (node (ref "XC6SLX9-144") (pin "143") (pinfunction "IO_L1N_VREF_0_143") (pintype "bidirectional"))
    )
    (net (code "33") (name "/ADC2_D12") (class "Default")
      (node (ref "XC6SLX9-144") (pin "142") (pinfunction "IO_L2P_0_142") (pintype "bidirectional"))
    )
    (net (code "34") (name "/ADC2_D13") (class "Default")
      (node (ref "XC6SLX9-144") (pin "141") (pinfunction "IO_L2N_0_141") (pintype "bidirectional"))
    )
    (net (code "35") (name "/ADC2_D14") (class "Default")
      (node (ref "XC6SLX9-144") (pin "140") (pinfunction "IO_L3P_0_140") (pintype "bidirectional"))
    )
    (net (code "36") (name "/ADC2_OTR") (class "Default")
      (node (ref "XC6SLX9-144") (pin "139") (pinfunction "IO_L3N_0_139") (pintype "bidirectional"))
    )
    (net (code "37") (name "/BT0") (class "Default")
      (node (ref "XC6SLX9-144") (pin "39") (pinfunction "IO_L65P_INIT_B_2_39") (pintype "bidirectional"))
    )
    (net (code "38") (name "/BT1") (class "Default")
      (node (ref "XC6SLX9-144") (pin "38") (pinfunction "IO_L65N_CSO_B_2_38") (pintype "bidirectional"))
    )
    (net (code "39") (name "/Ctr1") (class "Default")
      (node (ref "DIO2") (pin "8") (pinfunction "8_8") (pintype "passive"))
      (node (ref "XC6SLX9-144") (pin "104") (pinfunction "IO_L1N_VREF_1_104") (pintype "bidirectional"))
    )
    (net (code "40") (name "/Ctr2") (class "Default")
      (node (ref "DIO2") (pin "10") (pinfunction "10_10") (pintype "passive"))
      (node (ref "XC6SLX9-144") (pin "111") (pinfunction "IO_L66N_SCP0_0_111") (pintype "bidirectional"))
    )
    (net (code "41") (name "/Ctr3") (class "Default")
      (node (ref "DIO2") (pin "12") (pinfunction "12_12") (pintype "passive"))
      (node (ref "XC6SLX9-144") (pin "114") (pinfunction "IO_L65N_SCP2_0_114") (pintype "bidirectional"))
    )
    (net (code "42") (name "/D+") (class "Default")
      (node (ref "CH340B") (pin "5") (pinfunction "UD+_5") (pintype "bidirectional"))
      (node (ref "USB") (pin "3") (pinfunction "D+_3") (pintype "passive"))
    )
    (net (code "43") (name "/D-") (class "Default")
      (node (ref "CH340B") (pin "6") (pinfunction "UD-_6") (pintype "bidirectional"))
      (node (ref "USB") (pin "2") (pinfunction "D-_2") (pintype "passive"))
    )
    (net (code "44") (name "/D1") (class "Default")
      (node (ref "DIO2") (pin "1") (pinfunction "1_1") (pintype "passive"))
      (node (ref "XC6SLX9-144") (pin "98") (pinfunction "IO_L34P_1_98") (pintype "bidirectional"))
    )
    (net (code "45") (name "/D2") (class "Default")
      (node (ref "DIO2") (pin "3") (pinfunction "3_3") (pintype "passive"))
      (node (ref "XC6SLX9-144") (pin "100") (pinfunction "IO_L33P_1_100") (pintype "bidirectional"))
    )
    (net (code "46") (name "/D3") (class "Default")
      (node (ref "DIO2") (pin "5") (pinfunction "5_5") (pintype "passive"))
      (node (ref "XC6SLX9-144") (pin "102") (pinfunction "IO_L32P_1_102") (pintype "bidirectional"))
    )
    (net (code "47") (name "/D4") (class "Default")
      (node (ref "DIO2") (pin "7") (pinfunction "7_7") (pintype "passive"))
      (node (ref "XC6SLX9-144") (pin "105") (pinfunction "IO_L1P_1_105") (pintype "bidirectional"))
    )
    (net (code "48") (name "/D5") (class "Default")
      (node (ref "DIO2") (pin "9") (pinfunction "9_9") (pintype "passive"))
      (node (ref "XC6SLX9-144") (pin "112") (pinfunction "IO_L66P_SCP1_0_112") (pintype "bidirectional"))
    )
    (net (code "49") (name "/D6") (class "Default")
      (node (ref "DIO2") (pin "2") (pinfunction "2_2") (pintype "passive"))
      (node (ref "XC6SLX9-144") (pin "97") (pinfunction "IO_L34N_1_97") (pintype "bidirectional"))
    )
    (net (code "50") (name "/D7") (class "Default")
      (node (ref "DIO2") (pin "4") (pinfunction "4_4") (pintype "passive"))
      (node (ref "XC6SLX9-144") (pin "99") (pinfunction "IO_L33N_1_99") (pintype "bidirectional"))
    )
    (net (code "51") (name "/D8") (class "Default")
      (node (ref "DIO2") (pin "6") (pinfunction "6_6") (pintype "passive"))
      (node (ref "XC6SLX9-144") (pin "101") (pinfunction "IO_L32N_1_101") (pintype "bidirectional"))
    )
    (net (code "52") (name "/DAC904_CLK") (class "Default")
      (node (ref "U1") (pin "28") (pinfunction "CLK_28") (pintype "passive"))
      (node (ref "XC6SLX9-144") (pin "40") (pinfunction "IO_L64N_D9_2_40") (pintype "bidirectional"))
    )
    (net (code "53") (name "/DAC904_D1") (class "Default")
      (node (ref "U1") (pin "1") (pinfunction "D1_1") (pintype "passive"))
      (node (ref "XC6SLX9-144") (pin "35") (pinfunction "IO_L1P_3_35") (pintype "bidirectional"))
    )
    (net (code "54") (name "/DAC904_D2") (class "Default")
      (node (ref "U1") (pin "2") (pinfunction "D2_2") (pintype "passive"))
      (node (ref "XC6SLX9-144") (pin "34") (pinfunction "IO_L1N_VREF_3_34") (pintype "bidirectional"))
    )
    (net (code "55") (name "/DAC904_D3") (class "Default")
      (node (ref "U1") (pin "3") (pinfunction "D3_3") (pintype "passive"))
      (node (ref "XC6SLX9-144") (pin "33") (pinfunction "IO_L2P_3_33") (pintype "bidirectional"))
    )
    (net (code "56") (name "/DAC904_D4") (class "Default")
      (node (ref "U1") (pin "4") (pinfunction "D4_4") (pintype "passive"))
      (node (ref "XC6SLX9-144") (pin "32") (pinfunction "IO_L2N_3_32") (pintype "bidirectional"))
    )
    (net (code "57") (name "/DAC904_D5") (class "Default")
      (node (ref "U1") (pin "5") (pinfunction "D5_5") (pintype "passive"))
      (node (ref "XC6SLX9-144") (pin "30") (pinfunction "IO_L36P_3_30") (pintype "bidirectional"))
    )
    (net (code "58") (name "/DAC904_D6") (class "Default")
      (node (ref "U1") (pin "6") (pinfunction "D6_6") (pintype "passive"))
      (node (ref "XC6SLX9-144") (pin "29") (pinfunction "IO_L36N_3_29") (pintype "bidirectional"))
    )
    (net (code "59") (name "/DAC904_D7") (class "Default")
      (node (ref "U1") (pin "7") (pinfunction "D7_7") (pintype "passive"))
      (node (ref "XC6SLX9-144") (pin "27") (pinfunction "IO_L37P_3_27") (pintype "bidirectional"))
    )
    (net (code "60") (name "/DAC904_D8") (class "Default")
      (node (ref "U1") (pin "8") (pinfunction "D8_8") (pintype "passive"))
      (node (ref "XC6SLX9-144") (pin "26") (pinfunction "IO_L37N_3_26") (pintype "bidirectional"))
    )
    (net (code "61") (name "/DAC904_D9") (class "Default")
      (node (ref "U1") (pin "9") (pinfunction "D9_9") (pintype "passive"))
      (node (ref "XC6SLX9-144") (pin "24") (pinfunction "IO_L41P_GCLK27_3_24") (pintype "bidirectional"))
    )
    (net (code "62") (name "/DAC904_D10") (class "Default")
      (node (ref "U1") (pin "10") (pinfunction "D10_10") (pintype "passive"))
      (node (ref "XC6SLX9-144") (pin "23") (pinfunction "IO_L41N_GCLK26_3_23") (pintype "bidirectional"))
    )
    (net (code "63") (name "/DAC904_D11") (class "Default")
      (node (ref "U1") (pin "11") (pinfunction "D11_11") (pintype "passive"))
      (node (ref "XC6SLX9-144") (pin "22") (pinfunction "IO_L42P_GCLK25_TRDY2_3_22") (pintype "bidirectional"))
    )
    (net (code "64") (name "/DAC904_D12") (class "Default")
      (node (ref "U1") (pin "12") (pinfunction "D12_12") (pintype "passive"))
      (node (ref "XC6SLX9-144") (pin "21") (pinfunction "IO_L42N_GCLK24_3_21") (pintype "bidirectional"))
    )
    (net (code "65") (name "/DAC904_D13") (class "Default")
      (node (ref "U1") (pin "13") (pinfunction "D13_13") (pintype "passive"))
      (node (ref "XC6SLX9-144") (pin "17") (pinfunction "IO_L43P_GCLK23_3_17") (pintype "bidirectional"))
    )
    (net (code "66") (name "/DAC904_D14") (class "Default")
      (node (ref "U1") (pin "14") (pinfunction "D14_14") (pintype "passive"))
      (node (ref "XC6SLX9-144") (pin "16") (pinfunction "IO_L43N_GCLK22_IRDY2_3_16") (pintype "bidirectional"))
    )
    (net (code "67") (name "/DAC8551_CLK") (class "Default")
      (node (ref "U2") (pin "6") (pinfunction "SCLK_6") (pintype "passive"))
      (node (ref "XC6SLX9-144") (pin "14") (pinfunction "IO_L44N_GCLK20_3_14") (pintype "bidirectional"))
    )
    (net (code "68") (name "/DAC8551_CLK_Bias") (class "Default")
      (node (ref "U7") (pin "6") (pinfunction "SCLK_6") (pintype "passive"))
      (node (ref "XC6SLX9-144") (pin "43") (pinfunction "IO_L62N_D6_2_43") (pintype "bidirectional"))
    )
    (net (code "69") (name "/DAC8551_DIN") (class "Default")
      (node (ref "U2") (pin "7") (pinfunction "DIN_7") (pintype "passive"))
      (node (ref "XC6SLX9-144") (pin "12") (pinfunction "IO_L49P_3_12") (pintype "bidirectional"))
    )
    (net (code "70") (name "/DAC8551_DIN_Bias") (class "Default")
      (node (ref "U7") (pin "7") (pinfunction "DIN_7") (pintype "passive"))
      (node (ref "XC6SLX9-144") (pin "44") (pinfunction "IO_L62P_D5_2_44") (pintype "bidirectional"))
    )
    (net (code "71") (name "/DAC8551_SYN") (class "Default")
      (node (ref "U2") (pin "5") (pinfunction "SYNC_5") (pintype "passive"))
      (node (ref "XC6SLX9-144") (pin "15") (pinfunction "IO_L44P_GCLK21_3_15") (pintype "bidirectional"))
    )
    (net (code "72") (name "/DAC8551_SYN_Bias") (class "Default")
      (node (ref "U7") (pin "5") (pinfunction "SYNC_5") (pintype "passive"))
      (node (ref "XC6SLX9-144") (pin "41") (pinfunction "IO_L64P_D8_2_41") (pintype "bidirectional"))
    )
    (net (code "73") (name "/DC_Output") (class "Default")
      (node (ref "DC_Output") (pin "1") (pinfunction "1_1") (pintype "passive"))
      (node (ref "R31") (pin "2") (pinfunction "2_2") (pintype "passive"))
      (node (ref "R42") (pin "1") (pinfunction "1_1") (pintype "passive"))
      (node (ref "U12") (pin "1") (pinfunction "OUT_A_1") (pintype "passive"))
    )
    (net (code "74") (name "/DIO_1") (class "Default")
      (node (ref "DIO1") (pin "1") (pinfunction "1_1") (pintype "passive"))
      (node (ref "XC6SLX9-144") (pin "75") (pinfunction "IO_L74P_AWAKE_1_75") (pintype "bidirectional"))
    )
    (net (code "75") (name "/DIO_2") (class "Default")
      (node (ref "DIO1") (pin "2") (pinfunction "2_2") (pintype "passive"))
      (node (ref "XC6SLX9-144") (pin "74") (pinfunction "IO_L74N_DOUT_BUSY_1_74") (pintype "bidirectional"))
    )
    (net (code "76") (name "/DIO_3") (class "Default")
      (node (ref "DIO1") (pin "3") (pinfunction "3_3") (pintype "passive"))
      (node (ref "XC6SLX9-144") (pin "79") (pinfunction "IO_L47P_1_79") (pintype "bidirectional"))
    )
    (net (code "77") (name "/DIO_4") (class "Default")
      (node (ref "DIO1") (pin "4") (pinfunction "4_4") (pintype "passive"))
      (node (ref "XC6SLX9-144") (pin "78") (pinfunction "IO_L47N_1_78") (pintype "bidirectional"))
    )
    (net (code "78") (name "/DIO_5") (class "Default")
      (node (ref "DIO1") (pin "5") (pinfunction "5_5") (pintype "passive"))
      (node (ref "XC6SLX9-144") (pin "81") (pinfunction "IO_L46P_1_81") (pintype "bidirectional"))
    )
    (net (code "79") (name "/DIO_6") (class "Default")
      (node (ref "DIO1") (pin "6") (pinfunction "6_6") (pintype "passive"))
      (node (ref "XC6SLX9-144") (pin "80") (pinfunction "IO_L46N_1_80") (pintype "bidirectional"))
    )
    (net (code "80") (name "/DIO_7") (class "Default")
      (node (ref "DIO1") (pin "7") (pinfunction "7_7") (pintype "passive"))
      (node (ref "XC6SLX9-144") (pin "83") (pinfunction "IO_L45P_1_83") (pintype "bidirectional"))
    )
    (net (code "81") (name "/DIO_8") (class "Default")
      (node (ref "DIO1") (pin "8") (pinfunction "8_8") (pintype "passive"))
      (node (ref "XC6SLX9-144") (pin "82") (pinfunction "IO_L45N_1_82") (pintype "bidirectional"))
    )
    (net (code "82") (name "/DIO_9") (class "Default")
      (node (ref "DIO1") (pin "9") (pinfunction "9_9") (pintype "passive"))
      (node (ref "XC6SLX9-144") (pin "85") (pinfunction "IO_L43P_GCLK5_1_85") (pintype "bidirectional"))
    )
    (net (code "83") (name "/DIO_10") (class "Default")
      (node (ref "DIO1") (pin "10") (pinfunction "10_10") (pintype "passive"))
      (node (ref "XC6SLX9-144") (pin "84") (pinfunction "IO_L43N_GCLK4_1_84") (pintype "bidirectional"))
    )
    (net (code "84") (name "/DIO_11") (class "Default")
      (node (ref "DIO1") (pin "11") (pinfunction "11_11") (pintype "passive"))
      (node (ref "XC6SLX9-144") (pin "88") (pinfunction "IO_L42P_GCLK7_1_88") (pintype "bidirectional"))
    )
    (net (code "85") (name "/DIO_12") (class "Default")
      (node (ref "DIO1") (pin "12") (pinfunction "12_12") (pintype "passive"))
      (node (ref "XC6SLX9-144") (pin "87") (pinfunction "IO_L42N_GCLK6_TRDY1_1_87") (pintype "bidirectional"))
    )
    (net (code "86") (name "/DIO_13") (class "Default")
      (node (ref "DIO1") (pin "13") (pinfunction "13_13") (pintype "passive"))
      (node (ref "XC6SLX9-144") (pin "93") (pinfunction "IO_L41P_GCLK9_IRDY1_1_93") (pintype "bidirectional"))
    )
    (net (code "87") (name "/DIO_14") (class "Default")
      (node (ref "DIO1") (pin "14") (pinfunction "14_14") (pintype "passive"))
      (node (ref "XC6SLX9-144") (pin "92") (pinfunction "IO_L41N_GCLK8_1_92") (pintype "bidirectional"))
    )
    (net (code "88") (name "/DIO_15") (class "Default")
      (node (ref "DIO1") (pin "15") (pinfunction "15_15") (pintype "passive"))
      (node (ref "XC6SLX9-144") (pin "62") (pinfunction "IO_L12P_D1_MISO2_2_62") (pintype "bidirectional"))
    )
    (net (code "89") (name "/DIO_16") (class "Default")
      (node (ref "DIO1") (pin "16") (pinfunction "16_16") (pintype "passive"))
      (node (ref "XC6SLX9-144") (pin "67") (pinfunction "IO_L2P_CMPCLK_2_67") (pintype "bidirectional"))
    )
    (net (code "90") (name "/DIO_17") (class "Default")
      (node (ref "DIO1") (pin "17") (pinfunction "17_17") (pintype "passive"))
      (node (ref "XC6SLX9-144") (pin "58") (pinfunction "IO_L14P_D11_2_58") (pintype "bidirectional"))
    )
    (net (code "91") (name "/DIO_18") (class "Default")
      (node (ref "DIO1") (pin "18") (pinfunction "18_18") (pintype "passive"))
      (node (ref "XC6SLX9-144") (pin "59") (pinfunction "IO_L13N_D10_2_59") (pintype "bidirectional"))
    )
    (net (code "92") (name "/DIO_19") (class "Default")
      (node (ref "DIO1") (pin "19") (pinfunction "19_19") (pintype "passive"))
      (node (ref "XC6SLX9-144") (pin "55") (pinfunction "IO_L30N_GCLK0_USERCCLK_2_55") (pintype "bidirectional"))
    )
    (net (code "93") (name "/DIO_20") (class "Default")
      (node (ref "DIO1") (pin "20") (pinfunction "20_20") (pintype "passive"))
      (node (ref "XC6SLX9-144") (pin "57") (pinfunction "IO_L14N_D12_2_57") (pintype "bidirectional"))
    )
    (net (code "94") (name "/DIO_21") (class "Default")
      (node (ref "XC6SLX9-144") (pin "48") (pinfunction "IO_L48P_D7_2_48") (pintype "bidirectional"))
    )
    (net (code "95") (name "/DIO_22") (class "Default")
      (node (ref "XC6SLX9-144") (pin "51") (pinfunction "IO_L31P_GCLK31_D14_2_51") (pintype "bidirectional"))
    )
    (net (code "96") (name "/DONE") (class "Default")
      (node (ref "D5") (pin "1") (pinfunction "A_1") (pintype "passive"))
      (node (ref "R18") (pin "1") (pinfunction "1_1") (pintype "passive"))
      (node (ref "XC6SLX9-144") (pin "71") (pinfunction "DONE_2_71") (pintype "bidirectional"))
    )
    (net (code "97") (name "/GCLK_50M") (class "Default")
      (node (ref "C68") (pin "2") (pinfunction "2_2") (pintype "passive"))
      (node (ref "X1") (pin "3") (pinfunction "OUT_3") (pintype "passive"))
      (node (ref "XC6SLX9-144") (pin "56") (pinfunction "IO_L30P_GCLK1_D13_2_56") (pintype "bidirectional"))
    )
    (net (code "98") (name "/IOUT+") (class "Default")
      (node (ref "C19") (pin "2") (pinfunction "2_2") (pintype "passive"))
      (node (ref "R12") (pin "1") (pinfunction "1_1") (pintype "passive"))
      (node (ref "R8") (pin "1") (pinfunction "1_1") (pintype "passive"))
      (node (ref "U1") (pin "22") (pinfunction "IOUT_22") (pintype "passive"))
    )
    (net (code "99") (name "/IOUT-") (class "Default")
      (node (ref "C19") (pin "1") (pinfunction "1_1") (pintype "passive"))
      (node (ref "R11") (pin "1") (pinfunction "1_1") (pintype "passive"))
      (node (ref "R9") (pin "1") (pinfunction "1_1") (pintype "passive"))
      (node (ref "U1") (pin "21") (pinfunction "~{IOUT}_21") (pintype "passive"))
    )
    (net (code "100") (name "/LED0") (class "Default")
      (node (ref "R2") (pin "2") (pinfunction "2_2") (pintype "passive"))
      (node (ref "XC6SLX9-144") (pin "46") (pinfunction "IO_L49P_D3_2_46") (pintype "bidirectional"))
    )
    (net (code "101") (name "/LED1") (class "Default")
      (node (ref "R4") (pin "2") (pinfunction "2_2") (pintype "passive"))
      (node (ref "XC6SLX9-144") (pin "47") (pinfunction "IO_L48N_RDWR_B_VREF_2_47") (pintype "bidirectional"))
    )
    (net (code "102") (name "/M0") (class "Default")
      (node (ref "R22") (pin "1") (pinfunction "1_1") (pintype "passive"))
      (node (ref "XC6SLX9-144") (pin "69") (pinfunction "IO_L1N_M0_CMPMISO_2_69") (pintype "bidirectional"))
    )
    (net (code "103") (name "/M1") (class "Default")
      (node (ref "R20") (pin "1") (pinfunction "1_1") (pintype "passive"))
      (node (ref "XC6SLX9-144") (pin "60") (pinfunction "IO_L13P_M1_2_60") (pintype "bidirectional"))
    )
    (net (code "104") (name "/MISO") (class "Default")
      (node (ref "U25") (pin "2") (pinfunction "SO_2") (pintype "passive"))
      (node (ref "XC6SLX9-144") (pin "65") (pinfunction "IO_L3P_D0_DIN_MISO_MISO1_2_65") (pintype "bidirectional"))
    )
    (net (code "105") (name "/MOSI") (class "Default")
      (node (ref "U25") (pin "5") (pinfunction "SI_5") (pintype "passive"))
      (node (ref "XC6SLX9-144") (pin "64") (pinfunction "IO_L3N_MOSI_CSI_B_MISO0_2_64") (pintype "bidirectional"))
    )
    (net (code "106") (name "/PROG_B") (class "Default")
      (node (ref "R21") (pin "1") (pinfunction "1_1") (pintype "passive"))
      (node (ref "XC6SLX9-144") (pin "37") (pinfunction "PROGRAM_B_2_37") (pintype "input"))
    )
    (net (code "107") (name "/RXD") (class "Default")
      (node (ref "CH340B") (pin "3") (pinfunction "RXD_3") (pintype "input"))
      (node (ref "XC6SLX9-144") (pin "94") (pinfunction "IO_L40N_GCLK10_1_94") (pintype "bidirectional"))
    )
    (net (code "108") (name "/Ref_In") (class "Default")
      (node (ref "C62") (pin "1") (pinfunction "1_1") (pintype "passive"))
      (node (ref "U1") (pin "17") (pinfunction "REFin_17") (pintype "passive"))
      (node (ref "U2") (pin "3") (pinfunction "VFB_3") (pintype "passive"))
      (node (ref "U2") (pin "4") (pinfunction "Vout_4") (pintype "passive"))
    )
    (net (code "109") (name "/SCK") (class "Default")
      (node (ref "R26") (pin "1") (pinfunction "1_1") (pintype "passive"))
      (node (ref "U25") (pin "6") (pinfunction "CLK_6") (pintype "passive"))
      (node (ref "XC6SLX9-144") (pin "70") (pinfunction "IO_L1P_CCLK_2_70") (pintype "bidirectional"))
    )
    (net (code "110") (name "/SS") (class "Default")
      (node (ref "R24") (pin "1") (pinfunction "1_1") (pintype "passive"))
      (node (ref "U25") (pin "1") (pinfunction "CS_1") (pintype "passive"))
    )
    (net (code "111") (name "/TCK") (class "Default")
      (node (ref "JTAG") (pin "1") (pinfunction "TCK_1") (pintype "passive"))
      (node (ref "XC6SLX9-144") (pin "109") (pinfunction "TCK_109") (pintype "input"))
    )
    (net (code "112") (name "/TDI") (class "Default")
      (node (ref "JTAG") (pin "5") (pinfunction "TDI_5") (pintype "passive"))
      (node (ref "XC6SLX9-144") (pin "110") (pinfunction "TDI_110") (pintype "input"))
    )
    (net (code "113") (name "/TDO") (class "Default")
      (node (ref "JTAG") (pin "2") (pinfunction "TDO_2") (pintype "passive"))
      (node (ref "XC6SLX9-144") (pin "106") (pinfunction "TDO_106") (pintype "output"))
    )
    (net (code "114") (name "/TMS") (class "Default")
      (node (ref "JTAG") (pin "3") (pinfunction "TMS_3") (pintype "passive"))
      (node (ref "XC6SLX9-144") (pin "107") (pinfunction "TMS_107") (pintype "input"))
    )
    (net (code "115") (name "/TXD") (class "Default")
      (node (ref "CH340B") (pin "2") (pinfunction "TXD_2") (pintype "output"))
      (node (ref "XC6SLX9-144") (pin "95") (pinfunction "IO_L40P_GCLK11_1_95") (pintype "bidirectional"))
    )
    (net (code "116") (name "/UART2_RX") (class "Default")
      (node (ref "UART") (pin "2") (pinfunction "2_2") (pintype "passive"))
      (node (ref "XC6SLX9-144") (pin "50") (pinfunction "IO_L31N_GCLK30_D15_2_50") (pintype "bidirectional"))
    )
    (net (code "117") (name "/UART2_TX") (class "Default")
      (node (ref "UART") (pin "1") (pinfunction "1_1") (pintype "passive"))
      (node (ref "XC6SLX9-144") (pin "45") (pinfunction "IO_L49N_D4_2_45") (pintype "bidirectional"))
    )
    (net (code "118") (name "3V3") (class "Default")
      (node (ref "C0") (pin "2") (pinfunction "2_2") (pintype "passive"))
      (node (ref "C26") (pin "1") (pinfunction "1_1") (pintype "passive"))
      (node (ref "C36") (pin "2") (pinfunction "2_2") (pintype "passive"))
      (node (ref "C37") (pin "2") (pinfunction "2_2") (pintype "passive"))
      (node (ref "C38") (pin "2") (pinfunction "2_2") (pintype "passive"))
      (node (ref "C39") (pin "2") (pinfunction "2_2") (pintype "passive"))
      (node (ref "C40") (pin "2") (pinfunction "2_2") (pintype "passive"))
      (node (ref "C41") (pin "2") (pinfunction "2_2") (pintype "passive"))
      (node (ref "C42") (pin "2") (pinfunction "2_2") (pintype "passive"))
      (node (ref "C43") (pin "2") (pinfunction "2_2") (pintype "passive"))
      (node (ref "C44") (pin "2") (pinfunction "2_2") (pintype "passive"))
      (node (ref "C47") (pin "1") (pinfunction "1_1") (pintype "passive"))
      (node (ref "C48") (pin "1") (pinfunction "1_1") (pintype "passive"))
      (node (ref "C49") (pin "1") (pinfunction "1_1") (pintype "passive"))
      (node (ref "C50") (pin "1") (pinfunction "1_1") (pintype "passive"))
      (node (ref "C58") (pin "1") (pinfunction "1_1") (pintype "passive"))
      (node (ref "C60") (pin "2") (pinfunction "2_2") (pintype "passive"))
      (node (ref "C66") (pin "2") (pinfunction "2_2") (pintype "passive"))
      (node (ref "C67") (pin "1") (pinfunction "1_1") (pintype "passive"))
      (node (ref "C69") (pin "1") (pinfunction "1_1") (pintype "passive"))
      (node (ref "C92") (pin "2") (pinfunction "2_2") (pintype "passive"))
      (node (ref "C93") (pin "2") (pinfunction "2_2") (pintype "passive"))
      (node (ref "C94") (pin "2") (pinfunction "2_2") (pintype "passive"))
      (node (ref "D1") (pin "1") (pinfunction "A_1") (pintype "passive"))
      (node (ref "D3") (pin "1") (pinfunction "A_1") (pintype "passive"))
      (node (ref "DIO2") (pin "17") (pinfunction "17_17") (pintype "passive"))
      (node (ref "DIO2") (pin "18") (pinfunction "18_18") (pintype "passive"))
      (node (ref "DIO2") (pin "19") (pinfunction "19_19") (pintype "passive"))
      (node (ref "DIO2") (pin "20") (pinfunction "20_20") (pintype "passive"))
      (node (ref "JTAG") (pin "9") (pinfunction "VDD_9") (pintype "passive"))
      (node (ref "R18") (pin "2") (pinfunction "2_2") (pintype "passive"))
      (node (ref "R21") (pin "2") (pinfunction "2_2") (pintype "passive"))
      (node (ref "R22") (pin "2") (pinfunction "2_2") (pintype "passive"))
      (node (ref "R23") (pin "2") (pinfunction "2_2") (pintype "passive"))
      (node (ref "R24") (pin "2") (pinfunction "2_2") (pintype "passive"))
      (node (ref "R25") (pin "2") (pinfunction "2_2") (pintype "passive"))
      (node (ref "R26") (pin "2") (pinfunction "2_2") (pintype "passive"))
      (node (ref "U1") (pin "27") (pinfunction "+Vd_27") (pintype "passive"))
      (node (ref "U15") (pin "2") (pinfunction "OUT_2") (pintype "passive"))
      (node (ref "U25") (pin "8") (pinfunction "Vcc_8") (pintype "passive"))
      (node (ref "X1") (pin "4") (pinfunction "VCC_4") (pintype "passive"))
      (node (ref "XC6SLX9-144") (pin "103") (pinfunction "VCCO_1_103") (pintype "power_in"))
      (node (ref "XC6SLX9-144") (pin "122") (pinfunction "VCCO_0_122") (pintype "power_in"))
      (node (ref "XC6SLX9-144") (pin "125") (pinfunction "VCCO_0_125") (pintype "power_in"))
      (node (ref "XC6SLX9-144") (pin "129") (pinfunction "VCCAUX_129") (pintype "power_in"))
      (node (ref "XC6SLX9-144") (pin "135") (pinfunction "VCCO_0_135") (pintype "power_in"))
      (node (ref "XC6SLX9-144") (pin "18") (pinfunction "VCCO_3_18") (pintype "power_in"))
      (node (ref "XC6SLX9-144") (pin "20") (pinfunction "VCCAUX_20") (pintype "power_in"))
      (node (ref "XC6SLX9-144") (pin "31") (pinfunction "VCCO_3_31") (pintype "power_in"))
      (node (ref "XC6SLX9-144") (pin "36") (pinfunction "VCCAUX_36") (pintype "power_in"))
      (node (ref "XC6SLX9-144") (pin "4") (pinfunction "VCCO_3_4") (pintype "power_in"))
      (node (ref "XC6SLX9-144") (pin "42") (pinfunction "VCCO_2_42") (pintype "power_in"))
      (node (ref "XC6SLX9-144") (pin "53") (pinfunction "VCCAUX_53") (pintype "power_in"))
      (node (ref "XC6SLX9-144") (pin "63") (pinfunction "VCCO_2_63") (pintype "power_in"))
      (node (ref "XC6SLX9-144") (pin "76") (pinfunction "VCCO_1_76") (pintype "power_in"))
      (node (ref "XC6SLX9-144") (pin "86") (pinfunction "VCCO_1_86") (pintype "power_in"))
      (node (ref "XC6SLX9-144") (pin "90") (pinfunction "VCCAUX_90") (pintype "power_in"))
    )
    (net (code "119") (name "AGND") (class "Default")
      (node (ref "C1") (pin "1") (pinfunction "1_1") (pintype "passive"))
      (node (ref "C10") (pin "2") (pinfunction "2_2") (pintype "passive"))
      (node (ref "C105") (pin "1") (pinfunction "1_1") (pintype "passive"))
      (node (ref "C107") (pin "2") (pinfunction "2_2") (pintype "passive"))
      (node (ref "C12") (pin "1") (pinfunction "1_1") (pintype "passive"))
      (node (ref "C13") (pin "2") (pinfunction "2_2") (pintype "passive"))
      (node (ref "C14") (pin "1") (pinfunction "1_1") (pintype "passive"))
      (node (ref "C15") (pin "2") (pinfunction "2_2") (pintype "passive"))
      (node (ref "C17") (pin "2") (pinfunction "2_2") (pintype "passive"))
      (node (ref "C18") (pin "2") (pinfunction "2_2") (pintype "passive"))
      (node (ref "C2") (pin "2") (pinfunction "2_2") (pintype "passive"))
      (node (ref "C21") (pin "2") (pinfunction "2_2") (pintype "passive"))
      (node (ref "C22") (pin "2") (pinfunction "2_2") (pintype "passive"))
      (node (ref "C23") (pin "2") (pinfunction "2_2") (pintype "passive"))
      (node (ref "C24") (pin "2") (pinfunction "2_2") (pintype "passive"))
      (node (ref "C30") (pin "2") (pinfunction "2_2") (pintype "passive"))
      (node (ref "C31") (pin "2") (pinfunction "2_2") (pintype "passive"))
      (node (ref "C4") (pin "2") (pinfunction "2_2") (pintype "passive"))
      (node (ref "C6") (pin "2") (pinfunction "2_2") (pintype "passive"))
      (node (ref "C62") (pin "2") (pinfunction "2_2") (pintype "passive"))
      (node (ref "C7") (pin "1") (pinfunction "1_1") (pintype "passive"))
      (node (ref "C70") (pin "2") (pinfunction "2_2") (pintype "passive"))
      (node (ref "C71") (pin "2") (pinfunction "2_2") (pintype "passive"))
      (node (ref "C76") (pin "1") (pinfunction "1_1") (pintype "passive"))
      (node (ref "C77") (pin "2") (pinfunction "2_2") (pintype "passive"))
      (node (ref "C78") (pin "2") (pinfunction "2_2") (pintype "passive"))
      (node (ref "C79") (pin "2") (pinfunction "2_2") (pintype "passive"))
      (node (ref "C87") (pin "1") (pinfunction "1_1") (pintype "passive"))
      (node (ref "C88") (pin "2") (pinfunction "2_2") (pintype "passive"))
      (node (ref "C9") (pin "1") (pinfunction "1_1") (pintype "passive"))
      (node (ref "L2") (pin "2") (pinfunction "2_2") (pintype "passive"))
      (node (ref "Power") (pin "2") (pinfunction "2_2") (pintype "passive"))
      (node (ref "R10") (pin "1") (pinfunction "1_1") (pintype "passive"))
      (node (ref "R11") (pin "2") (pinfunction "2_2") (pintype "passive"))
      (node (ref "R12") (pin "2") (pinfunction "2_2") (pintype "passive"))
      (node (ref "R40") (pin "2") (pinfunction "2_2") (pintype "passive"))
      (node (ref "R5") (pin "1") (pinfunction "1_1") (pintype "passive"))
      (node (ref "SigOut") (pin "2") (pinfunction "Y_2") (pintype "passive"))
      (node (ref "U1") (pin "20") (pinfunction "AGND_20") (pintype "passive"))
      (node (ref "U2") (pin "8") (pinfunction "GND_8") (pintype "passive"))
      (node (ref "U3") (pin "1") (pinfunction "GND_F_1") (pintype "passive"))
      (node (ref "U3") (pin "2") (pinfunction "GND_S_2") (pintype "passive"))
      (node (ref "U6") (pin "1") (pinfunction "GND_F_1") (pintype "passive"))
      (node (ref "U6") (pin "2") (pinfunction "GND_S_2") (pintype "passive"))
      (node (ref "U7") (pin "8") (pinfunction "GND_8") (pintype "passive"))
    )
    (net (code "120") (name "DGND") (class "Default")
      (node (ref "C0") (pin "1") (pinfunction "1_1") (pintype "passive"))
      (node (ref "C26") (pin "2") (pinfunction "2_2") (pintype "passive"))
      (node (ref "C33") (pin "2") (pinfunction "2_2") (pintype "passive"))
      (node (ref "C34") (pin "2") (pinfunction "2_2") (pintype "passive"))
      (node (ref "C35") (pin "2") (pinfunction "2_2") (pintype "passive"))
      (node (ref "C36") (pin "1") (pinfunction "1_1") (pintype "passive"))
      (node (ref "C37") (pin "1") (pinfunction "1_1") (pintype "passive"))
      (node (ref "C38") (pin "1") (pinfunction "1_1") (pintype "passive"))
      (node (ref "C39") (pin "1") (pinfunction "1_1") (pintype "passive"))
      (node (ref "C40") (pin "1") (pinfunction "1_1") (pintype "passive"))
      (node (ref "C41") (pin "1") (pinfunction "1_1") (pintype "passive"))
      (node (ref "C42") (pin "1") (pinfunction "1_1") (pintype "passive"))
      (node (ref "C43") (pin "1") (pinfunction "1_1") (pintype "passive"))
      (node (ref "C44") (pin "1") (pinfunction "1_1") (pintype "passive"))
      (node (ref "C45") (pin "1") (pinfunction "1_1") (pintype "passive"))
      (node (ref "C46") (pin "1") (pinfunction "1_1") (pintype "passive"))
      (node (ref "C47") (pin "2") (pinfunction "2_2") (pintype "passive"))
      (node (ref "C48") (pin "2") (pinfunction "2_2") (pintype "passive"))
      (node (ref "C49") (pin "2") (pinfunction "2_2") (pintype "passive"))
      (node (ref "C50") (pin "2") (pinfunction "2_2") (pintype "passive"))
      (node (ref "C51") (pin "2") (pinfunction "2_2") (pintype "passive"))
      (node (ref "C56") (pin "1") (pinfunction "1_1") (pintype "passive"))
      (node (ref "C57") (pin "1") (pinfunction "1_1") (pintype "passive"))
      (node (ref "C58") (pin "2") (pinfunction "2_2") (pintype "passive"))
      (node (ref "C59") (pin "2") (pinfunction "2_2") (pintype "passive"))
      (node (ref "C60") (pin "1") (pinfunction "1_1") (pintype "passive"))
      (node (ref "C61") (pin "1") (pinfunction "1_1") (pintype "passive"))
      (node (ref "C64") (pin "2") (pinfunction "2_2") (pintype "passive"))
      (node (ref "C65") (pin "2") (pinfunction "2_2") (pintype "passive"))
      (node (ref "C66") (pin "1") (pinfunction "1_1") (pintype "passive"))
      (node (ref "C67") (pin "2") (pinfunction "2_2") (pintype "passive"))
      (node (ref "C68") (pin "1") (pinfunction "1_1") (pintype "passive"))
      (node (ref "C69") (pin "2") (pinfunction "2_2") (pintype "passive"))
      (node (ref "C90") (pin "1") (pinfunction "1_1") (pintype "passive"))
      (node (ref "C91") (pin "1") (pinfunction "1_1") (pintype "passive"))
      (node (ref "C92") (pin "1") (pinfunction "1_1") (pintype "passive"))
      (node (ref "C93") (pin "1") (pinfunction "1_1") (pintype "passive"))
      (node (ref "C94") (pin "1") (pinfunction "1_1") (pintype "passive"))
      (node (ref "CH340B") (pin "1") (pinfunction "GND_1") (pintype "power_in"))
      (node (ref "DIO2") (pin "11") (pinfunction "11_11") (pintype "passive"))
      (node (ref "DIO2") (pin "13") (pinfunction "13_13") (pintype "passive"))
      (node (ref "DIO2") (pin "14") (pinfunction "14_14") (pintype "passive"))
      (node (ref "DIO2") (pin "15") (pinfunction "15_15") (pintype "passive"))
      (node (ref "DIO2") (pin "16") (pinfunction "16_16") (pintype "passive"))
      (node (ref "JTAG") (pin "10") (pinfunction "GND_10") (pintype "passive"))
      (node (ref "JTAG") (pin "6") (pinfunction "GND_6") (pintype "passive"))
      (node (ref "L1") (pin "1") (pinfunction "1_1") (pintype "passive"))
      (node (ref "L2") (pin "1") (pinfunction "1_1") (pintype "passive"))
      (node (ref "R19") (pin "2") (pinfunction "2_2") (pintype "passive"))
      (node (ref "R20") (pin "2") (pinfunction "2_2") (pintype "passive"))
      (node (ref "U1") (pin "26") (pinfunction "DGND_26") (pintype "passive"))
      (node (ref "U14") (pin "1") (pinfunction "GND_1") (pintype "passive"))
      (node (ref "U15") (pin "1") (pinfunction "GND_1") (pintype "passive"))
      (node (ref "U25") (pin "4") (pinfunction "GND_4") (pintype "passive"))
      (node (ref "UART") (pin "3") (pinfunction "3_3") (pintype "passive"))
      (node (ref "USB") (pin "4") (pinfunction "GND_4") (pintype "passive"))
      (node (ref "X1") (pin "2") (pinfunction "GND_2") (pintype "passive"))
      (node (ref "XC6SLX9-144") (pin "108") (pinfunction "GND_108") (pintype "power_in"))
      (node (ref "XC6SLX9-144") (pin "113") (pinfunction "GND_113") (pintype "power_in"))
      (node (ref "XC6SLX9-144") (pin "13") (pinfunction "GND_13") (pintype "power_in"))
      (node (ref "XC6SLX9-144") (pin "130") (pinfunction "GND_130") (pintype "power_in"))
      (node (ref "XC6SLX9-144") (pin "136") (pinfunction "GND_136") (pintype "power_in"))
      (node (ref "XC6SLX9-144") (pin "25") (pinfunction "GND_25") (pintype "power_in"))
      (node (ref "XC6SLX9-144") (pin "3") (pinfunction "GND_3") (pintype "power_in"))
      (node (ref "XC6SLX9-144") (pin "49") (pinfunction "GND_49") (pintype "power_in"))
      (node (ref "XC6SLX9-144") (pin "54") (pinfunction "GND_54") (pintype "power_in"))
      (node (ref "XC6SLX9-144") (pin "68") (pinfunction "GND_68") (pintype "power_in"))
      (node (ref "XC6SLX9-144") (pin "73") (pinfunction "SUSPEND_73") (pintype "input"))
      (node (ref "XC6SLX9-144") (pin "77") (pinfunction "GND_77") (pintype "power_in"))
      (node (ref "XC6SLX9-144") (pin "91") (pinfunction "GND_91") (pintype "power_in"))
      (node (ref "XC6SLX9-144") (pin "96") (pinfunction "GND_96") (pintype "power_in"))
    )
    (net (code "121") (name "Net-(CH340B-V3)") (class "Default")
      (node (ref "C33") (pin "1") (pinfunction "1_1") (pintype "passive"))
      (node (ref "CH340B") (pin "4") (pinfunction "V3_4") (pintype "power_in"))
    )
    (net (code "122") (name "Net-(D1-K)") (class "Default")
      (node (ref "D1") (pin "2") (pinfunction "K_2") (pintype "passive"))
      (node (ref "R2") (pin "1") (pinfunction "1_1") (pintype "passive"))
    )
    (net (code "123") (name "Net-(D3-K)") (class "Default")
      (node (ref "D3") (pin "2") (pinfunction "K_2") (pintype "passive"))
      (node (ref "R4") (pin "1") (pinfunction "1_1") (pintype "passive"))
    )
    (net (code "124") (name "Net-(D5-K)") (class "Default")
      (node (ref "D5") (pin "2") (pinfunction "K_2") (pintype "passive"))
      (node (ref "R19") (pin "1") (pinfunction "1_1") (pintype "passive"))
    )
    (net (code "125") (name "Net-(L1-Pad2)") (class "Default")
      (node (ref "L1") (pin "2") (pinfunction "2_2") (pintype "passive"))
      (node (ref "USB") (pin "5") (pinfunction "VSS_5") (pintype "passive"))
      (node (ref "USB") (pin "6") (pinfunction "VSS_6") (pintype "passive"))
    )
    (net (code "126") (name "Net-(SigOut-X)") (class "Default")
      (node (ref "R43") (pin "2") (pinfunction "2_2") (pintype "passive"))
      (node (ref "SigOut") (pin "1") (pinfunction "X_1") (pintype "passive"))
      (node (ref "U13") (pin "6") (pinfunction "Vout_6") (pintype "passive"))
    )
    (net (code "127") (name "Net-(U1-BW)") (class "Default")
      (node (ref "C11") (pin "2") (pinfunction "2_2") (pintype "passive"))
      (node (ref "U1") (pin "19") (pinfunction "BW_19") (pintype "passive"))
    )
    (net (code "128") (name "Net-(U1-BYP)") (class "Default")
      (node (ref "C10") (pin "1") (pinfunction "1_1") (pintype "passive"))
      (node (ref "U1") (pin "23") (pinfunction "BYP_23") (pintype "passive"))
    )
    (net (code "129") (name "Net-(U1-FSA)") (class "Default")
      (node (ref "R5") (pin "2") (pinfunction "2_2") (pintype "passive"))
      (node (ref "U1") (pin "18") (pinfunction "FSA_18") (pintype "passive"))
    )
    (net (code "130") (name "Net-(U2-VRef)") (class "Default")
      (node (ref "C12") (pin "2") (pinfunction "2_2") (pintype "passive"))
      (node (ref "C17") (pin "1") (pinfunction "1_1") (pintype "passive"))
      (node (ref "U2") (pin "2") (pinfunction "VRef_2") (pintype "passive"))
      (node (ref "U3") (pin "5") (pinfunction "VOUT_S_5") (pintype "passive"))
      (node (ref "U3") (pin "6") (pinfunction "VOUT_F_6") (pintype "passive"))
    )
    (net (code "131") (name "Net-(U6-VOUT_F)") (class "Default")
      (node (ref "C13") (pin "1") (pinfunction "1_1") (pintype "passive"))
      (node (ref "C14") (pin "2") (pinfunction "2_2") (pintype "passive"))
      (node (ref "R30") (pin "2") (pinfunction "2_2") (pintype "passive"))
      (node (ref "U6") (pin "5") (pinfunction "VOUT_S_5") (pintype "passive"))
      (node (ref "U6") (pin "6") (pinfunction "VOUT_F_6") (pintype "passive"))
      (node (ref "U7") (pin "2") (pinfunction "VRef_2") (pintype "passive"))
    )
    (net (code "132") (name "Net-(U10-IN+)") (class "Default")
      (node (ref "R10") (pin "2") (pinfunction "2_2") (pintype "passive"))
      (node (ref "R9") (pin "2") (pinfunction "2_2") (pintype "passive"))
      (node (ref "U10") (pin "3") (pinfunction "IN+_3") (pintype "passive"))
    )
    (net (code "133") (name "Net-(U10-IN-)") (class "Default")
      (node (ref "C89") (pin "1") (pinfunction "1_1") (pintype "passive"))
      (node (ref "R7") (pin "1") (pinfunction "1_1") (pintype "passive"))
      (node (ref "R8") (pin "2") (pinfunction "2_2") (pintype "passive"))
      (node (ref "U10") (pin "2") (pinfunction "IN-_2") (pintype "passive"))
    )
    (net (code "134") (name "Net-(U12-+IN)") (class "Default")
      (node (ref "U12") (pin "3") (pinfunction "+IN_3") (pintype "passive"))
      (node (ref "U7") (pin "3") (pinfunction "VFB_3") (pintype "passive"))
      (node (ref "U7") (pin "4") (pinfunction "Vout_4") (pintype "passive"))
    )
    (net (code "135") (name "Net-(U12--IN)") (class "Default")
      (node (ref "R30") (pin "1") (pinfunction "1_1") (pintype "passive"))
      (node (ref "R31") (pin "1") (pinfunction "1_1") (pintype "passive"))
      (node (ref "U12") (pin "4") (pinfunction "-IN_4") (pintype "passive"))
    )
    (net (code "136") (name "Net-(U13-IN+)") (class "Default")
      (node (ref "R40") (pin "1") (pinfunction "1_1") (pintype "passive"))
      (node (ref "R41") (pin "2") (pinfunction "2_2") (pintype "passive"))
      (node (ref "U13") (pin "3") (pinfunction "IN+_3") (pintype "passive"))
    )
    (net (code "137") (name "Net-(U13-IN-)") (class "Default")
      (node (ref "R42") (pin "2") (pinfunction "2_2") (pintype "passive"))
      (node (ref "R43") (pin "1") (pinfunction "1_1") (pintype "passive"))
      (node (ref "U13") (pin "2") (pinfunction "IN-_2") (pintype "passive"))
    )
    (net (code "138") (name "Net-(U25-HOLD)") (class "Default")
      (node (ref "R23") (pin "1") (pinfunction "1_1") (pintype "passive"))
      (node (ref "U25") (pin "7") (pinfunction "HOLD_7") (pintype "passive"))
    )
    (net (code "139") (name "Net-(U25-{slash}WP)") (class "Default")
      (node (ref "R25") (pin "1") (pinfunction "1_1") (pintype "passive"))
      (node (ref "U25") (pin "3") (pinfunction "/WP_3") (pintype "passive"))
    )
    (net (code "140") (name "USB5V") (class "Default")
      (node (ref "C34") (pin "1") (pinfunction "1_1") (pintype "passive"))
      (node (ref "C35") (pin "1") (pinfunction "1_1") (pintype "passive"))
      (node (ref "CH340B") (pin "16") (pinfunction "VCC_16") (pintype "power_in"))
      (node (ref "USB") (pin "1") (pinfunction "Vcc_1") (pintype "passive"))
    )
    (net (code "141") (name "unconnected-(CH340B-CTS#-Pad9)") (class "Default")
      (node (ref "CH340B") (pin "9") (pinfunction "CTS#_9") (pintype "input+no_connect"))
    )
    (net (code "142") (name "unconnected-(CH340B-DCD#-Pad12)") (class "Default")
      (node (ref "CH340B") (pin "12") (pinfunction "DCD#_12") (pintype "input+no_connect"))
    )
    (net (code "143") (name "unconnected-(CH340B-DSR#-Pad10)") (class "Default")
      (node (ref "CH340B") (pin "10") (pinfunction "DSR#_10") (pintype "input+no_connect"))
    )
    (net (code "144") (name "unconnected-(CH340B-DTR#-Pad13)") (class "Default")
      (node (ref "CH340B") (pin "13") (pinfunction "DTR#_13") (pintype "output+no_connect"))
    )
    (net (code "145") (name "unconnected-(CH340B-R232-Pad15)") (class "Default")
      (node (ref "CH340B") (pin "15") (pinfunction "R232_15") (pintype "input+no_connect"))
    )
    (net (code "146") (name "unconnected-(CH340B-RI#-Pad11)") (class "Default")
      (node (ref "CH340B") (pin "11") (pinfunction "RI#_11") (pintype "input+no_connect"))
    )
    (net (code "147") (name "unconnected-(CH340B-RTS#-Pad14)") (class "Default")
      (node (ref "CH340B") (pin "14") (pinfunction "RTS#_14") (pintype "output+no_connect"))
    )
    (net (code "148") (name "unconnected-(CH340B-XI-Pad7)") (class "Default")
      (node (ref "CH340B") (pin "7") (pinfunction "XI_7") (pintype "input+no_connect"))
    )
    (net (code "149") (name "unconnected-(CH340B-XO-Pad8)") (class "Default")
      (node (ref "CH340B") (pin "8") (pinfunction "XO_8") (pintype "output+no_connect"))
    )
    (net (code "150") (name "unconnected-(JTAG-NULL-Pad4)") (class "Default")
      (node (ref "JTAG") (pin "4") (pinfunction "NULL_4") (pintype "passive"))
    )
    (net (code "151") (name "unconnected-(JTAG-NULL-Pad7)") (class "Default")
      (node (ref "JTAG") (pin "7") (pinfunction "NULL_7") (pintype "passive"))
    )
    (net (code "152") (name "unconnected-(JTAG-NULL-Pad8)") (class "Default")
      (node (ref "JTAG") (pin "8") (pinfunction "NULL_8") (pintype "passive"))
    )
    (net (code "153") (name "unconnected-(U1-NC-Pad25)") (class "Default")
      (node (ref "U1") (pin "25") (pinfunction "NC_25") (pintype "passive+no_connect"))
    )
    (net (code "154") (name "unconnected-(U1-PD-Pad15)") (class "Default")
      (node (ref "U1") (pin "15") (pinfunction "PD_15") (pintype "passive+no_connect"))
    )
    (net (code "155") (name "unconnected-(U10-NC-Pad1)") (class "Default")
      (node (ref "U10") (pin "1") (pinfunction "NC_1") (pintype "passive+no_connect"))
    )
    (net (code "156") (name "unconnected-(U10-NC-Pad5)") (class "Default")
      (node (ref "U10") (pin "5") (pinfunction "NC_5") (pintype "passive+no_connect"))
    )
    (net (code "157") (name "unconnected-(U10-NC-Pad8)") (class "Default")
      (node (ref "U10") (pin "8") (pinfunction "NC_8") (pintype "passive+no_connect"))
    )
    (net (code "158") (name "unconnected-(U13-NC-Pad1)") (class "Default")
      (node (ref "U13") (pin "1") (pinfunction "NC_1") (pintype "passive"))
    )
    (net (code "159") (name "unconnected-(U13-NC-Pad5)") (class "Default")
      (node (ref "U13") (pin "5") (pinfunction "NC_5") (pintype "passive"))
    )
    (net (code "160") (name "unconnected-(U13-NC-Pad8)") (class "Default")
      (node (ref "U13") (pin "8") (pinfunction "NC_8") (pintype "passive"))
    )
    (net (code "161") (name "unconnected-(X1-NC-Pad1)") (class "Default")
      (node (ref "X1") (pin "1") (pinfunction "NC_1") (pintype "passive"))
    )
    (net (code "162") (name "unconnected-(XC6SLX9-144C-IO_L2N_CMPMOSI_2-Pad66)") (class "Default")
      (node (ref "XC6SLX9-144") (pin "66") (pinfunction "IO_L2N_CMPMOSI_2_66") (pintype "bidirectional"))
    )
    (net (code "163") (name "unconnected-(XC6SLX9-144C-IO_L12N_D2_MISO3_2-Pad61)") (class "Default")
      (node (ref "XC6SLX9-144") (pin "61") (pinfunction "IO_L12N_D2_MISO3_2_61") (pintype "bidirectional"))
    )
    (net (code "164") (name "unconnected-(XC6SLX9-144E-CMPCS_B_2-Pad72)") (class "Default")
      (node (ref "XC6SLX9-144") (pin "72") (pinfunction "CMPCS_B_2_72") (pintype "input+no_connect"))
    )
  )
)
